# DeMux2.net
KiCad netlist of a schematic drawn in EAGLE
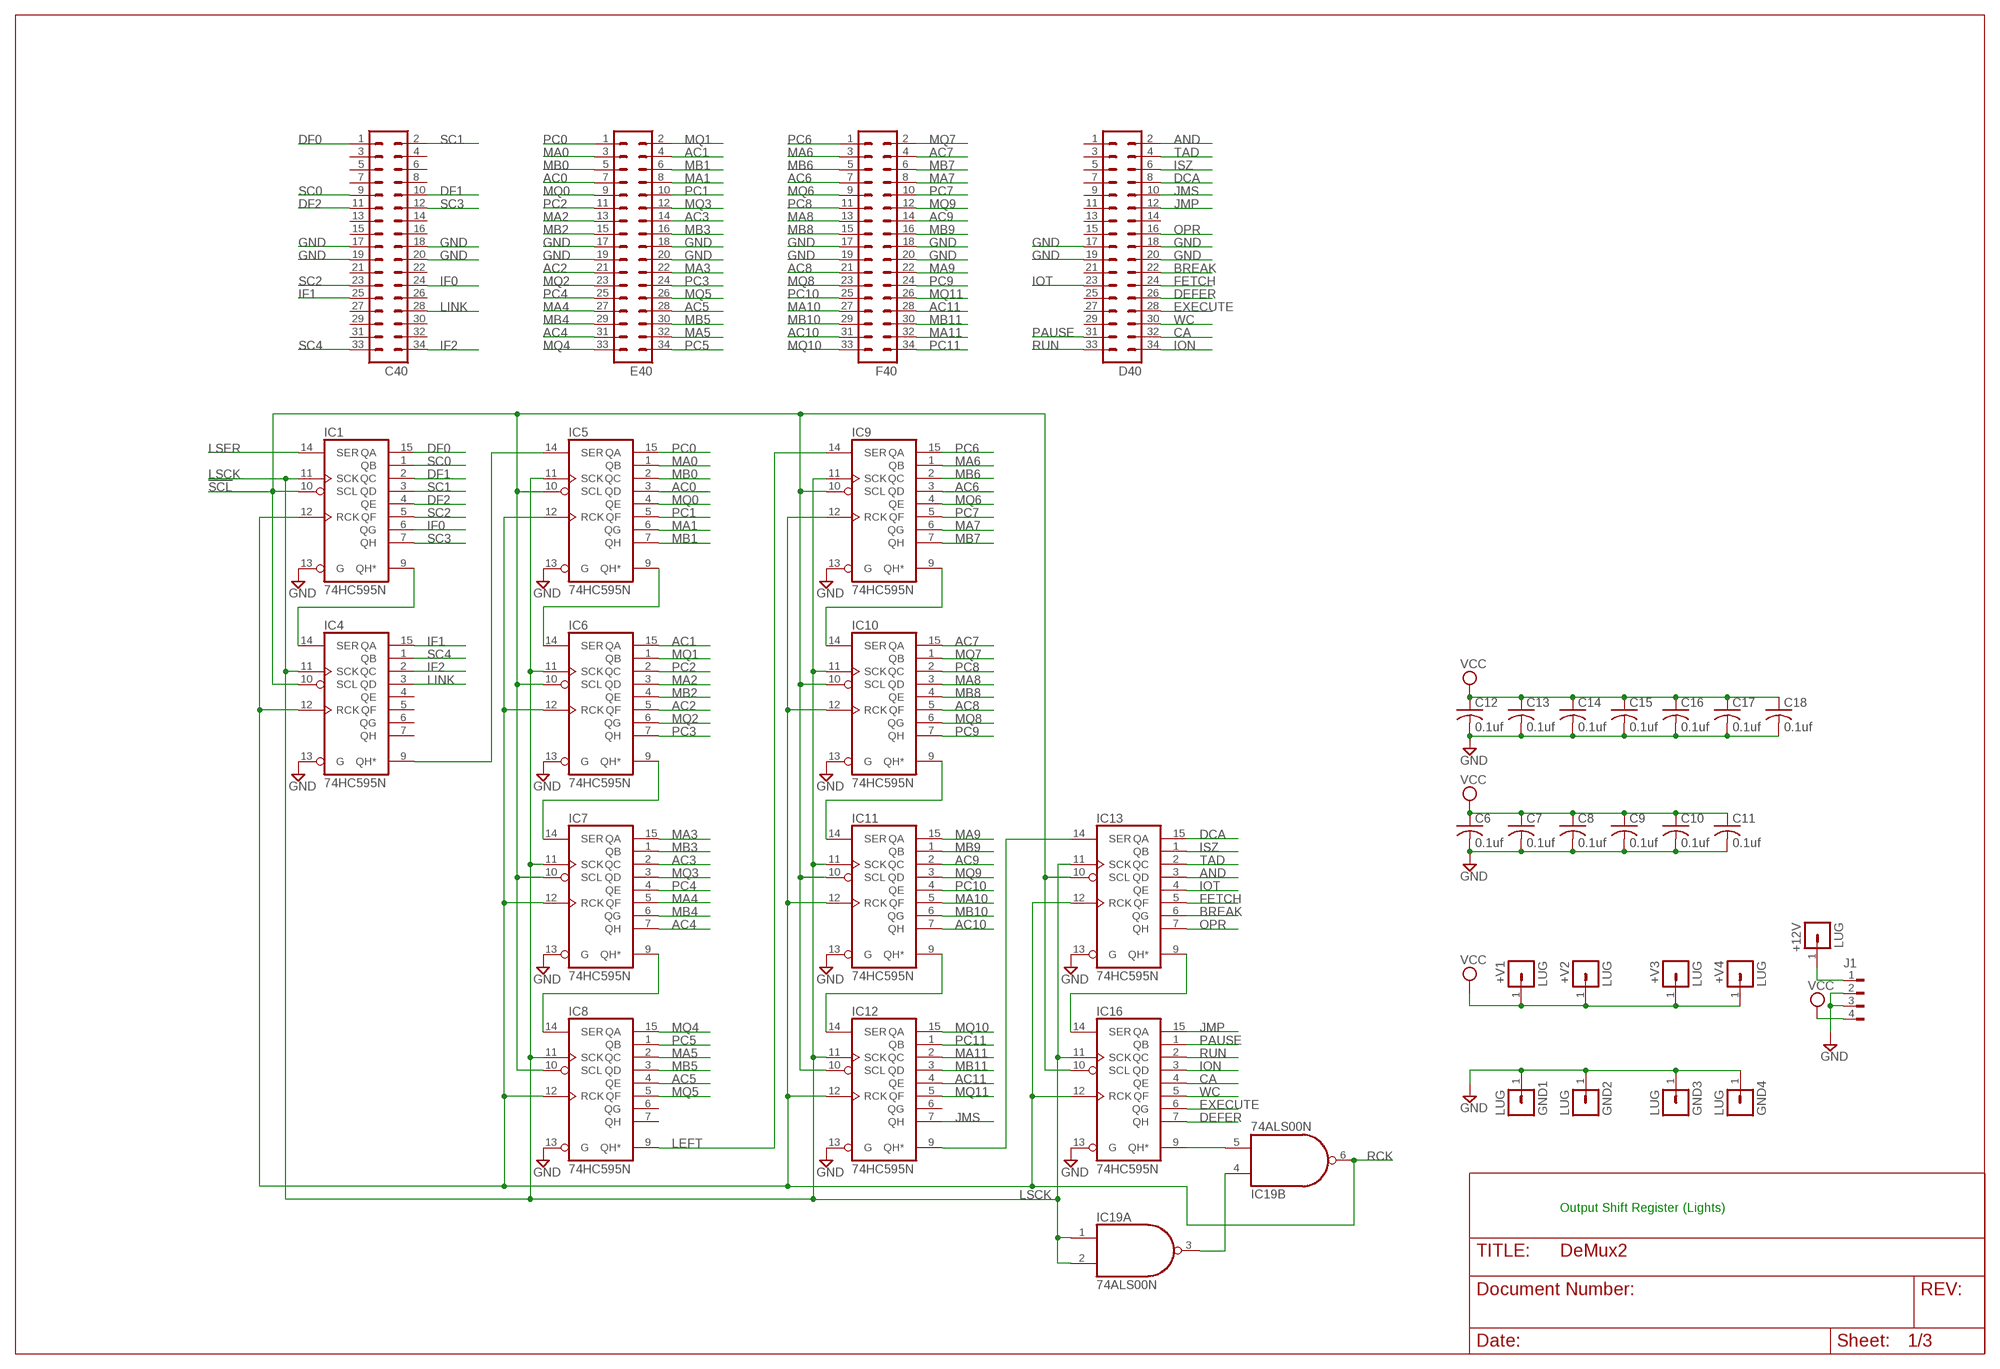
[diagram p0: schematic, sheet 1]
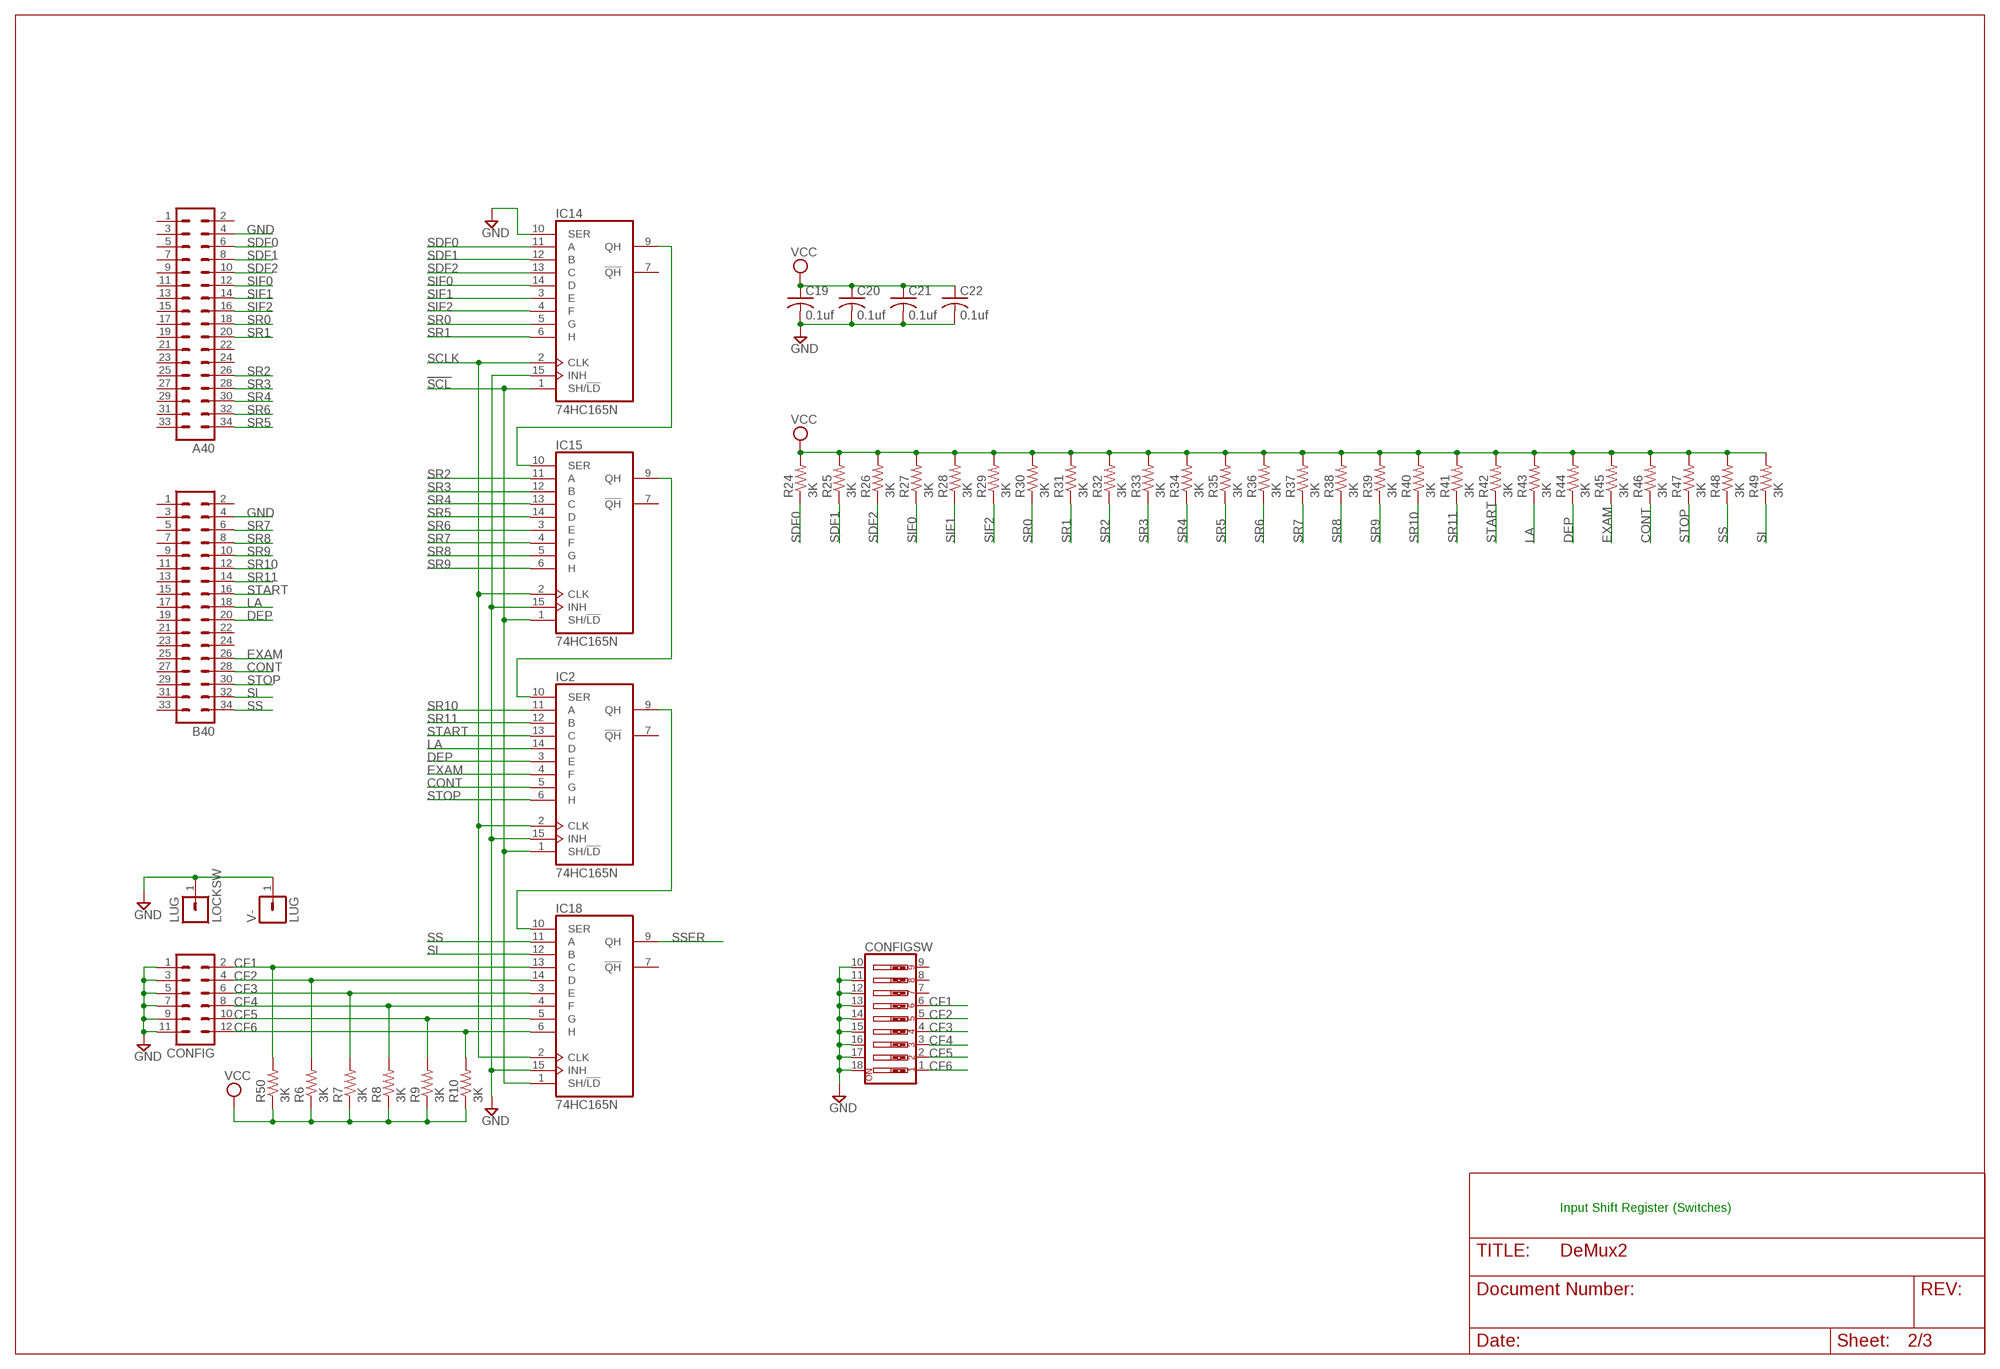
[diagram p1: schematic, sheet 2]
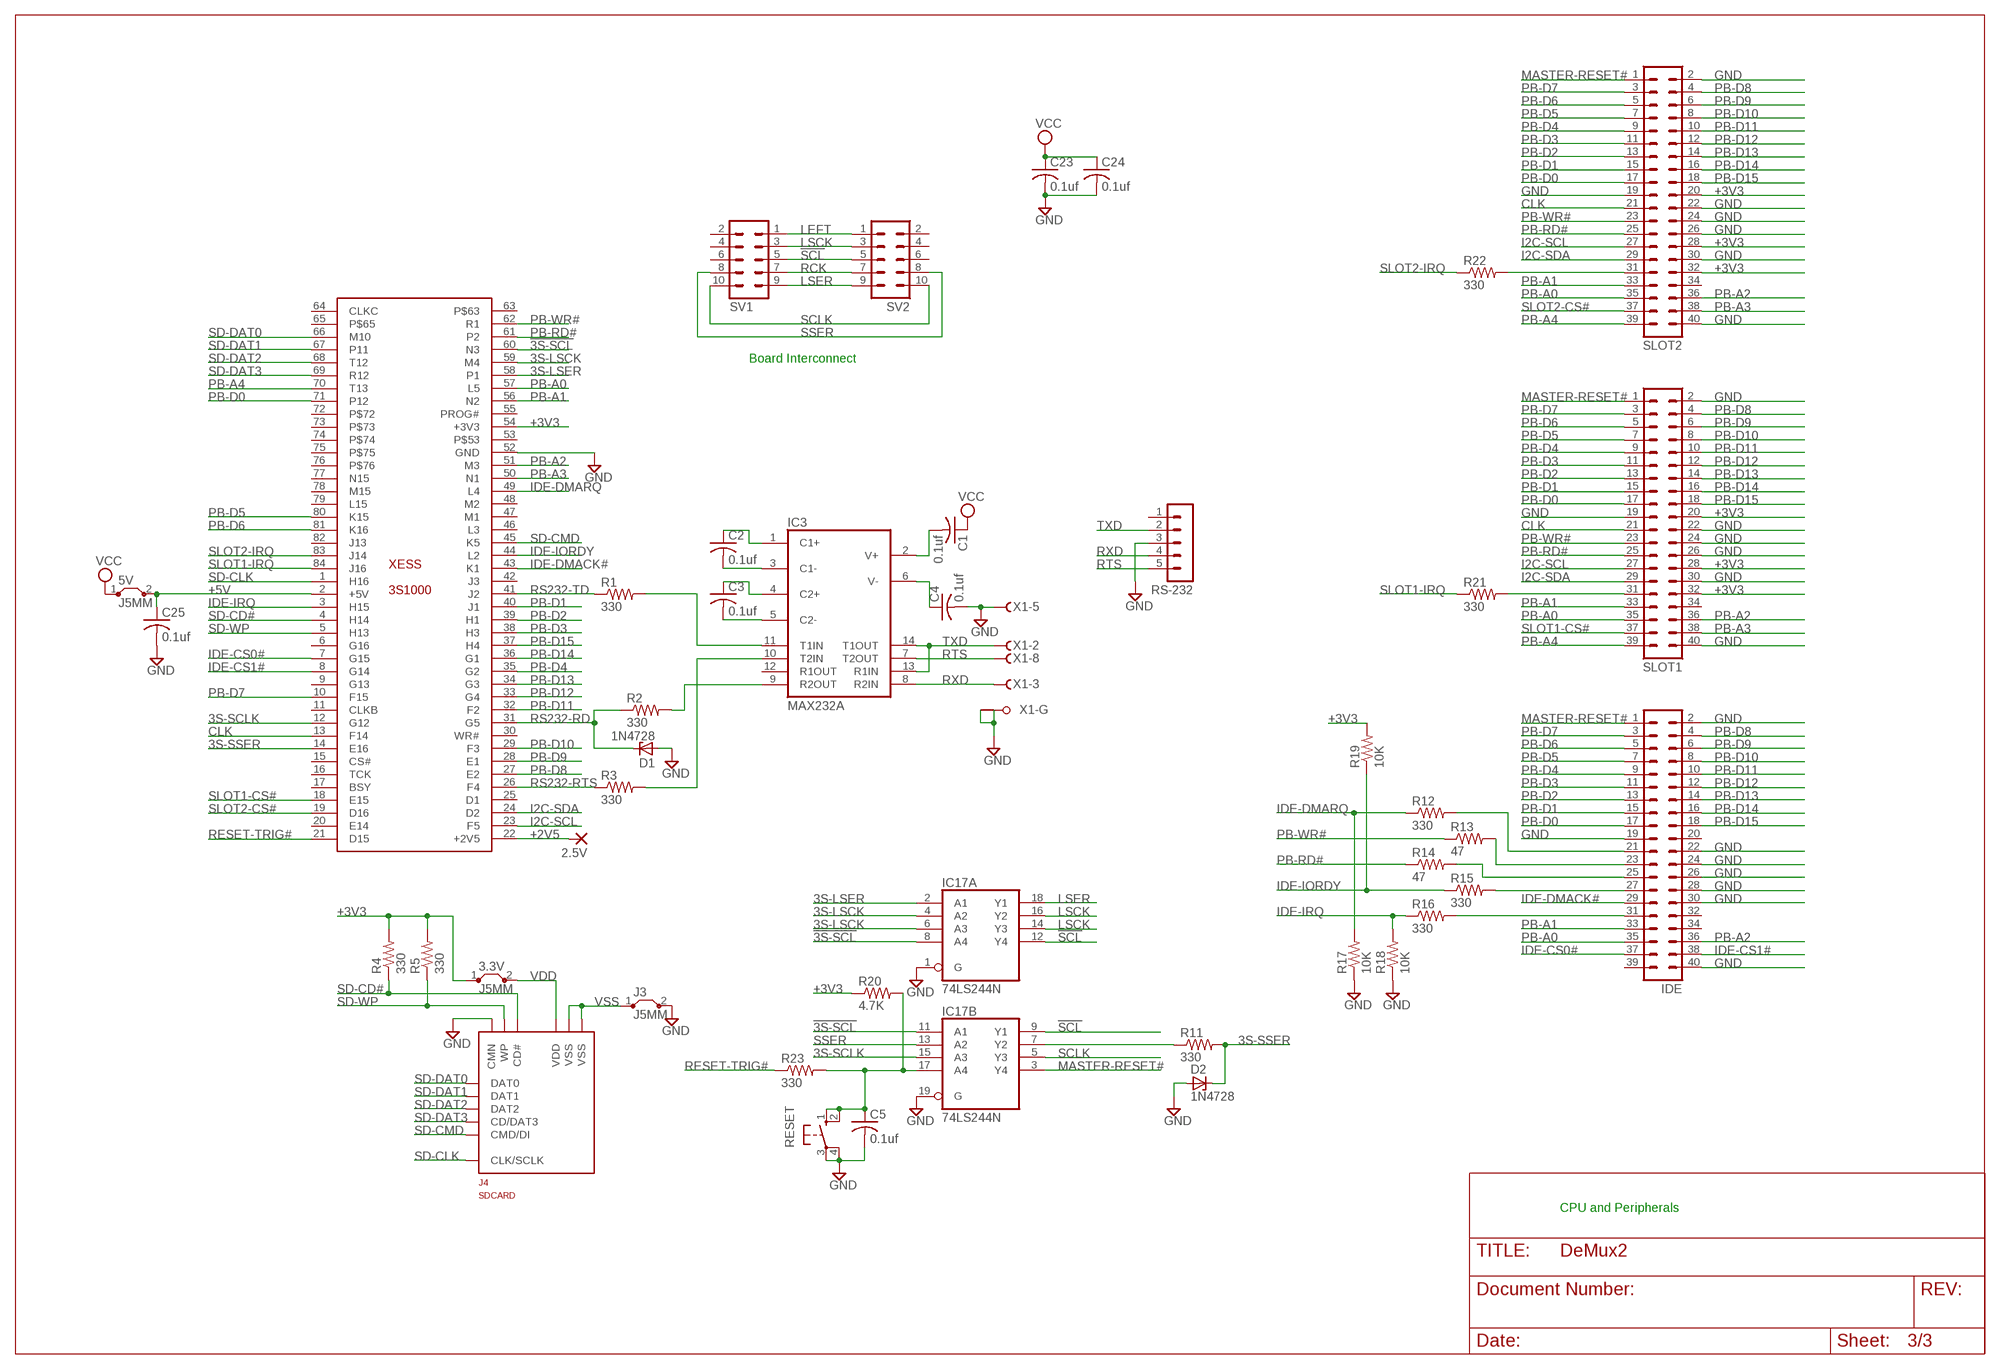
[diagram p2: schematic, sheet 3]

(export (version "E")
  (design (tool "Eeschema 10.0.6"))
  (components
    (comp (ref "2.5V")
      (value "1,6/0,8")
      (footprint "eagle-import:1,6_0,8")
      (libsource (lib "eagle-import") (part "1,6/0,8"))
    )
    (comp (ref "3.3V")
      (value "J5MM")
      (footprint "eagle-import:05")
      (libsource (lib "eagle-import") (part "J5MM"))
    )
    (comp (ref "5V")
      (value "J5MM")
      (footprint "eagle-import:05")
      (libsource (lib "eagle-import") (part "J5MM"))
    )
    (comp (ref "C1")
      (value "0.1uf")
      (footprint "eagle-import:C050-025X075")
      (libsource (lib "eagle-import") (part "C-US050-025X075"))
    )
    (comp (ref "C2")
      (value "0.1uf")
      (footprint "eagle-import:C050-025X075")
      (libsource (lib "eagle-import") (part "C-US050-025X075"))
    )
    (comp (ref "C3")
      (value "0.1uf")
      (footprint "eagle-import:C050-025X075")
      (libsource (lib "eagle-import") (part "C-US050-025X075"))
    )
    (comp (ref "C4")
      (value "0.1uf")
      (footprint "eagle-import:C050-025X075")
      (libsource (lib "eagle-import") (part "C-US050-025X075"))
    )
    (comp (ref "C5")
      (value "0.1uf")
      (footprint "eagle-import:C050-025X075")
      (libsource (lib "eagle-import") (part "C-US050-025X075"))
    )
    (comp (ref "C23")
      (value "0.1uf")
      (footprint "eagle-import:C050-025X075")
      (libsource (lib "eagle-import") (part "C-US050-025X075"))
    )
    (comp (ref "C24")
      (value "0.1uf")
      (footprint "eagle-import:C050-025X075")
      (libsource (lib "eagle-import") (part "C-US050-025X075"))
    )
    (comp (ref "C25")
      (value "0.1uf")
      (footprint "eagle-import:C050-025X075")
      (libsource (lib "eagle-import") (part "C-US050-025X075"))
    )
    (comp (ref "D1")
      (value "1N4728")
      (footprint "eagle-import:DO41Z10")
      (libsource (lib "eagle-import") (part "1N4728"))
    )
    (comp (ref "D2")
      (value "1N4728")
      (footprint "eagle-import:DO41Z10")
      (libsource (lib "eagle-import") (part "1N4728"))
    )
    (comp (ref "IC3")
      (value "MAX232A")
      (footprint "eagle-import:DIL16")
      (fields (field (name "MF") "MAXIM") (field (name "MPN") "MAX232ACPE+"))
      (libsource (lib "eagle-import") (part "MAX232"))
    )
    (comp (ref "IC17")
      (value "74LS244N")
      (footprint "eagle-import:DIL20")
      (libsource (lib "eagle-import") (part "74244NLS"))
    )
    (comp (ref "IDE")
      (value "MA20-2")
      (footprint "eagle-import:MA20-2")
      (libsource (lib "eagle-import") (part "MA20-2"))
    )
    (comp (ref "J3")
      (value "J5MM")
      (footprint "eagle-import:05")
      (libsource (lib "eagle-import") (part "J5MM"))
    )
    (comp (ref "J4")
      (value "SDCARD")
      (footprint "eagle-import:SCDA5A")
      (libsource (lib "eagle-import") (part "SDCARD"))
    )
    (comp (ref "R1")
      (value "330")
      (footprint "eagle-import:0207_10")
      (libsource (lib "eagle-import") (part "R-US_0207/10"))
    )
    (comp (ref "R2")
      (value "330")
      (footprint "eagle-import:0207_10")
      (libsource (lib "eagle-import") (part "R-US_0207/10"))
    )
    (comp (ref "R3")
      (value "330")
      (footprint "eagle-import:0207_10")
      (libsource (lib "eagle-import") (part "R-US_0207/10"))
    )
    (comp (ref "R4")
      (value "330")
      (footprint "eagle-import:0207_10")
      (libsource (lib "eagle-import") (part "R-US_0207/10"))
    )
    (comp (ref "R5")
      (value "330")
      (footprint "eagle-import:0207_10")
      (libsource (lib "eagle-import") (part "R-US_0207/10"))
    )
    (comp (ref "R11")
      (value "330")
      (footprint "eagle-import:0207_10")
      (libsource (lib "eagle-import") (part "R-US_0207/10"))
    )
    (comp (ref "R12")
      (value "330")
      (footprint "eagle-import:0207_10")
      (libsource (lib "eagle-import") (part "R-US_0207/10"))
    )
    (comp (ref "R13")
      (value "47")
      (footprint "eagle-import:0207_10")
      (libsource (lib "eagle-import") (part "R-US_0207/10"))
    )
    (comp (ref "R14")
      (value "47")
      (footprint "eagle-import:0207_10")
      (libsource (lib "eagle-import") (part "R-US_0207/10"))
    )
    (comp (ref "R15")
      (value "330")
      (footprint "eagle-import:0207_10")
      (libsource (lib "eagle-import") (part "R-US_0207/10"))
    )
    (comp (ref "R16")
      (value "330")
      (footprint "eagle-import:0207_10")
      (libsource (lib "eagle-import") (part "R-US_0207/10"))
    )
    (comp (ref "R17")
      (value "10K")
      (footprint "eagle-import:0207_10")
      (libsource (lib "eagle-import") (part "R-US_0207/10"))
    )
    (comp (ref "R18")
      (value "10K")
      (footprint "eagle-import:0207_10")
      (libsource (lib "eagle-import") (part "R-US_0207/10"))
    )
    (comp (ref "R19")
      (value "10K")
      (footprint "eagle-import:0207_10")
      (libsource (lib "eagle-import") (part "R-US_0207/10"))
    )
    (comp (ref "R20")
      (value "4.7K")
      (footprint "eagle-import:0207_10")
      (libsource (lib "eagle-import") (part "R-US_0207/10"))
    )
    (comp (ref "R21")
      (value "330")
      (footprint "eagle-import:0207_10")
      (libsource (lib "eagle-import") (part "R-US_0207/10"))
    )
    (comp (ref "R22")
      (value "330")
      (footprint "eagle-import:0207_10")
      (libsource (lib "eagle-import") (part "R-US_0207/10"))
    )
    (comp (ref "R23")
      (value "330")
      (footprint "eagle-import:0207_10")
      (libsource (lib "eagle-import") (part "R-US_0207/10"))
    )
    (comp (ref "RESET")
      (value "40-XX")
      (footprint "eagle-import:B3F-40XX")
      (fields (field (name "MF") "OMRON COMPONENTS USA") (field (name "MPN") "B3F-4000"))
      (libsource (lib "eagle-import") (part "40-XX"))
    )
    (comp (ref "RS-232")
      (value "MA05-1")
      (footprint "eagle-import:MA05-1")
      (libsource (lib "eagle-import") (part "MA05-1"))
    )
    (comp (ref "SLOT1")
      (value "MA20-2")
      (footprint "eagle-import:MA20-2")
      (libsource (lib "eagle-import") (part "MA20-2"))
    )
    (comp (ref "SLOT2")
      (value "MA20-2")
      (footprint "eagle-import:MA20-2")
      (libsource (lib "eagle-import") (part "MA20-2"))
    )
    (comp (ref "SV1")
      (value "MA05-2")
      (footprint "eagle-import:MA05-2")
      (libsource (lib "eagle-import") (part "MA05-2"))
    )
    (comp (ref "SV2")
      (value "MA05-2")
      (footprint "eagle-import:MA05-2")
      (libsource (lib "eagle-import") (part "MA05-2"))
    )
    (comp (ref "X1")
      (value "F09HPS")
      (footprint "eagle-import:F09HP")
      (libsource (lib "eagle-import") (part "F09HPS"))
    )
    (comp (ref "XESS")
      (value "3S1000")
      (footprint "eagle-import:3S1000")
      (libsource (lib "eagle-import") (part "3S1000"))
    )
    (comp (ref "+12V")
      (value "LUG")
      (footprint "eagle-import:SPADELUG")
      (libsource (lib "eagle-import") (part "LUG"))
    )
    (comp (ref "+V1")
      (value "LUG")
      (footprint "eagle-import:SPADELUG")
      (libsource (lib "eagle-import") (part "LUG"))
    )
    (comp (ref "+V2")
      (value "LUG")
      (footprint "eagle-import:SPADELUG")
      (libsource (lib "eagle-import") (part "LUG"))
    )
    (comp (ref "+V3")
      (value "LUG")
      (footprint "eagle-import:SPADELUG")
      (libsource (lib "eagle-import") (part "LUG"))
    )
    (comp (ref "+V4")
      (value "LUG")
      (footprint "eagle-import:SPADELUG")
      (libsource (lib "eagle-import") (part "LUG"))
    )
    (comp (ref "C6")
      (value "0.1uf")
      (footprint "eagle-import:C050-025X075")
      (libsource (lib "eagle-import") (part "C-US050-025X075"))
    )
    (comp (ref "C7")
      (value "0.1uf")
      (footprint "eagle-import:C050-025X075")
      (libsource (lib "eagle-import") (part "C-US050-025X075"))
    )
    (comp (ref "C8")
      (value "0.1uf")
      (footprint "eagle-import:C050-025X075")
      (libsource (lib "eagle-import") (part "C-US050-025X075"))
    )
    (comp (ref "C9")
      (value "0.1uf")
      (footprint "eagle-import:C050-025X075")
      (libsource (lib "eagle-import") (part "C-US050-025X075"))
    )
    (comp (ref "C10")
      (value "0.1uf")
      (footprint "eagle-import:C050-025X075")
      (libsource (lib "eagle-import") (part "C-US050-025X075"))
    )
    (comp (ref "C11")
      (value "0.1uf")
      (footprint "eagle-import:C050-025X075")
      (libsource (lib "eagle-import") (part "C-US050-025X075"))
    )
    (comp (ref "C12")
      (value "0.1uf")
      (footprint "eagle-import:C050-025X075")
      (libsource (lib "eagle-import") (part "C-US050-025X075"))
    )
    (comp (ref "C13")
      (value "0.1uf")
      (footprint "eagle-import:C050-025X075")
      (libsource (lib "eagle-import") (part "C-US050-025X075"))
    )
    (comp (ref "C14")
      (value "0.1uf")
      (footprint "eagle-import:C050-025X075")
      (libsource (lib "eagle-import") (part "C-US050-025X075"))
    )
    (comp (ref "C15")
      (value "0.1uf")
      (footprint "eagle-import:C050-025X075")
      (libsource (lib "eagle-import") (part "C-US050-025X075"))
    )
    (comp (ref "C16")
      (value "0.1uf")
      (footprint "eagle-import:C050-025X075")
      (libsource (lib "eagle-import") (part "C-US050-025X075"))
    )
    (comp (ref "C17")
      (value "0.1uf")
      (footprint "eagle-import:C050-025X075")
      (libsource (lib "eagle-import") (part "C-US050-025X075"))
    )
    (comp (ref "C18")
      (value "0.1uf")
      (footprint "eagle-import:C050-025X075")
      (libsource (lib "eagle-import") (part "C-US050-025X075"))
    )
    (comp (ref "C40")
      (value "MA17-2")
      (footprint "eagle-import:MA17-2")
      (libsource (lib "eagle-import") (part "MA17-2"))
    )
    (comp (ref "D40")
      (value "MA17-2")
      (footprint "eagle-import:MA17-2")
      (libsource (lib "eagle-import") (part "MA17-2"))
    )
    (comp (ref "E40")
      (value "MA17-2")
      (footprint "eagle-import:MA17-2")
      (libsource (lib "eagle-import") (part "MA17-2"))
    )
    (comp (ref "F40")
      (value "MA17-2")
      (footprint "eagle-import:MA17-2")
      (libsource (lib "eagle-import") (part "MA17-2"))
    )
    (comp (ref "GND1")
      (value "LUG")
      (footprint "eagle-import:SPADELUG")
      (libsource (lib "eagle-import") (part "LUG"))
    )
    (comp (ref "GND2")
      (value "LUG")
      (footprint "eagle-import:SPADELUG")
      (libsource (lib "eagle-import") (part "LUG"))
    )
    (comp (ref "GND3")
      (value "LUG")
      (footprint "eagle-import:SPADELUG")
      (libsource (lib "eagle-import") (part "LUG"))
    )
    (comp (ref "GND4")
      (value "LUG")
      (footprint "eagle-import:SPADELUG")
      (libsource (lib "eagle-import") (part "LUG"))
    )
    (comp (ref "IC1")
      (value "74HC595N")
      (footprint "eagle-import:DIL16")
      (libsource (lib "eagle-import") (part "74595NLS"))
    )
    (comp (ref "IC4")
      (value "74HC595N")
      (footprint "eagle-import:DIL16")
      (libsource (lib "eagle-import") (part "74595NLS"))
    )
    (comp (ref "IC5")
      (value "74HC595N")
      (footprint "eagle-import:DIL16")
      (libsource (lib "eagle-import") (part "74595NLS"))
    )
    (comp (ref "IC6")
      (value "74HC595N")
      (footprint "eagle-import:DIL16")
      (libsource (lib "eagle-import") (part "74595NLS"))
    )
    (comp (ref "IC7")
      (value "74HC595N")
      (footprint "eagle-import:DIL16")
      (libsource (lib "eagle-import") (part "74595NLS"))
    )
    (comp (ref "IC8")
      (value "74HC595N")
      (footprint "eagle-import:DIL16")
      (libsource (lib "eagle-import") (part "74595NLS"))
    )
    (comp (ref "IC9")
      (value "74HC595N")
      (footprint "eagle-import:DIL16")
      (libsource (lib "eagle-import") (part "74595NLS"))
    )
    (comp (ref "IC10")
      (value "74HC595N")
      (footprint "eagle-import:DIL16")
      (libsource (lib "eagle-import") (part "74595NLS"))
    )
    (comp (ref "IC11")
      (value "74HC595N")
      (footprint "eagle-import:DIL16")
      (libsource (lib "eagle-import") (part "74595NLS"))
    )
    (comp (ref "IC12")
      (value "74HC595N")
      (footprint "eagle-import:DIL16")
      (libsource (lib "eagle-import") (part "74595NLS"))
    )
    (comp (ref "IC13")
      (value "74HC595N")
      (footprint "eagle-import:DIL16")
      (libsource (lib "eagle-import") (part "74595NLS"))
    )
    (comp (ref "IC16")
      (value "74HC595N")
      (footprint "eagle-import:DIL16")
      (libsource (lib "eagle-import") (part "74595NLS"))
    )
    (comp (ref "IC19")
      (value "74ALS00N")
      (footprint "eagle-import:DIL14")
      (libsource (lib "eagle-import") (part "7400NALS"))
    )
    (comp (ref "J1")
      (value "FLOPPY-4")
      (footprint "eagle-import:FLOPPY-4")
      (libsource (lib "eagle-import") (part "FLOPPY-4"))
    )
    (comp (ref "A40")
      (value "MA17-2")
      (footprint "eagle-import:MA17-2")
      (libsource (lib "eagle-import") (part "MA17-2"))
    )
    (comp (ref "B40")
      (value "MA17-2")
      (footprint "eagle-import:MA17-2")
      (libsource (lib "eagle-import") (part "MA17-2"))
    )
    (comp (ref "C19")
      (value "0.1uf")
      (footprint "eagle-import:C050-025X075")
      (libsource (lib "eagle-import") (part "C-US050-025X075"))
    )
    (comp (ref "C20")
      (value "0.1uf")
      (footprint "eagle-import:C050-025X075")
      (libsource (lib "eagle-import") (part "C-US050-025X075"))
    )
    (comp (ref "C21")
      (value "0.1uf")
      (footprint "eagle-import:C050-025X075")
      (libsource (lib "eagle-import") (part "C-US050-025X075"))
    )
    (comp (ref "C22")
      (value "0.1uf")
      (footprint "eagle-import:C050-025X075")
      (libsource (lib "eagle-import") (part "C-US050-025X075"))
    )
    (comp (ref "CONFIG")
      (value "MA06-2")
      (footprint "eagle-import:MA06-2")
      (libsource (lib "eagle-import") (part "MA06-2"))
    )
    (comp (ref "CONFIGSW")
      (value "SW_DIP-9")
      (footprint "eagle-import:EDG-09")
      (libsource (lib "eagle-import") (part "SW_DIP-9"))
    )
    (comp (ref "IC2")
      (value "74HC165N")
      (footprint "eagle-import:DIL16")
      (libsource (lib "eagle-import") (part "74165NLS"))
    )
    (comp (ref "IC14")
      (value "74HC165N")
      (footprint "eagle-import:DIL16")
      (libsource (lib "eagle-import") (part "74165NLS"))
    )
    (comp (ref "IC15")
      (value "74HC165N")
      (footprint "eagle-import:DIL16")
      (libsource (lib "eagle-import") (part "74165NLS"))
    )
    (comp (ref "IC18")
      (value "74HC165N")
      (footprint "eagle-import:DIL16")
      (libsource (lib "eagle-import") (part "74165NLS"))
    )
    (comp (ref "LOCKSW")
      (value "LUG")
      (footprint "eagle-import:SPADELUG")
      (libsource (lib "eagle-import") (part "LUG"))
    )
    (comp (ref "R6")
      (value "3K")
      (footprint "eagle-import:0207_10")
      (libsource (lib "eagle-import") (part "R-US_0207/10"))
    )
    (comp (ref "R7")
      (value "3K")
      (footprint "eagle-import:0207_10")
      (libsource (lib "eagle-import") (part "R-US_0207/10"))
    )
    (comp (ref "R8")
      (value "3K")
      (footprint "eagle-import:0207_10")
      (libsource (lib "eagle-import") (part "R-US_0207/10"))
    )
    (comp (ref "R9")
      (value "3K")
      (footprint "eagle-import:0207_10")
      (libsource (lib "eagle-import") (part "R-US_0207/10"))
    )
    (comp (ref "R10")
      (value "3K")
      (footprint "eagle-import:0207_10")
      (libsource (lib "eagle-import") (part "R-US_0207/10"))
    )
    (comp (ref "R24")
      (value "3K")
      (footprint "eagle-import:0207_10")
      (libsource (lib "eagle-import") (part "R-US_0207/10"))
    )
    (comp (ref "R25")
      (value "3K")
      (footprint "eagle-import:0207_10")
      (libsource (lib "eagle-import") (part "R-US_0207/10"))
    )
    (comp (ref "R26")
      (value "3K")
      (footprint "eagle-import:0207_10")
      (libsource (lib "eagle-import") (part "R-US_0207/10"))
    )
    (comp (ref "R27")
      (value "3K")
      (footprint "eagle-import:0207_10")
      (libsource (lib "eagle-import") (part "R-US_0207/10"))
    )
    (comp (ref "R28")
      (value "3K")
      (footprint "eagle-import:0207_10")
      (libsource (lib "eagle-import") (part "R-US_0207/10"))
    )
    (comp (ref "R29")
      (value "3K")
      (footprint "eagle-import:0207_10")
      (libsource (lib "eagle-import") (part "R-US_0207/10"))
    )
    (comp (ref "R30")
      (value "3K")
      (footprint "eagle-import:0207_10")
      (libsource (lib "eagle-import") (part "R-US_0207/10"))
    )
    (comp (ref "R31")
      (value "3K")
      (footprint "eagle-import:0207_10")
      (libsource (lib "eagle-import") (part "R-US_0207/10"))
    )
    (comp (ref "R32")
      (value "3K")
      (footprint "eagle-import:0207_10")
      (libsource (lib "eagle-import") (part "R-US_0207/10"))
    )
    (comp (ref "R33")
      (value "3K")
      (footprint "eagle-import:0207_10")
      (libsource (lib "eagle-import") (part "R-US_0207/10"))
    )
    (comp (ref "R34")
      (value "3K")
      (footprint "eagle-import:0207_10")
      (libsource (lib "eagle-import") (part "R-US_0207/10"))
    )
    (comp (ref "R35")
      (value "3K")
      (footprint "eagle-import:0207_10")
      (libsource (lib "eagle-import") (part "R-US_0207/10"))
    )
    (comp (ref "R36")
      (value "3K")
      (footprint "eagle-import:0207_10")
      (libsource (lib "eagle-import") (part "R-US_0207/10"))
    )
    (comp (ref "R37")
      (value "3K")
      (footprint "eagle-import:0207_10")
      (libsource (lib "eagle-import") (part "R-US_0207/10"))
    )
    (comp (ref "R38")
      (value "3K")
      (footprint "eagle-import:0207_10")
      (libsource (lib "eagle-import") (part "R-US_0207/10"))
    )
    (comp (ref "R39")
      (value "3K")
      (footprint "eagle-import:0207_10")
      (libsource (lib "eagle-import") (part "R-US_0207/10"))
    )
    (comp (ref "R40")
      (value "3K")
      (footprint "eagle-import:0207_10")
      (libsource (lib "eagle-import") (part "R-US_0207/10"))
    )
    (comp (ref "R41")
      (value "3K")
      (footprint "eagle-import:0207_10")
      (libsource (lib "eagle-import") (part "R-US_0207/10"))
    )
    (comp (ref "R42")
      (value "3K")
      (footprint "eagle-import:0207_10")
      (libsource (lib "eagle-import") (part "R-US_0207/10"))
    )
    (comp (ref "R43")
      (value "3K")
      (footprint "eagle-import:0207_10")
      (libsource (lib "eagle-import") (part "R-US_0207/10"))
    )
    (comp (ref "R44")
      (value "3K")
      (footprint "eagle-import:0207_10")
      (libsource (lib "eagle-import") (part "R-US_0207/10"))
    )
    (comp (ref "R45")
      (value "3K")
      (footprint "eagle-import:0207_10")
      (libsource (lib "eagle-import") (part "R-US_0207/10"))
    )
    (comp (ref "R46")
      (value "3K")
      (footprint "eagle-import:0207_10")
      (libsource (lib "eagle-import") (part "R-US_0207/10"))
    )
    (comp (ref "R47")
      (value "3K")
      (footprint "eagle-import:0207_10")
      (libsource (lib "eagle-import") (part "R-US_0207/10"))
    )
    (comp (ref "R48")
      (value "3K")
      (footprint "eagle-import:0207_10")
      (libsource (lib "eagle-import") (part "R-US_0207/10"))
    )
    (comp (ref "R49")
      (value "3K")
      (footprint "eagle-import:0207_10")
      (libsource (lib "eagle-import") (part "R-US_0207/10"))
    )
    (comp (ref "R50")
      (value "3K")
      (footprint "eagle-import:0207_10")
      (libsource (lib "eagle-import") (part "R-US_0207/10"))
    )
    (comp (ref "V-")
      (value "LUG")
      (footprint "eagle-import:SPADELUG")
      (libsource (lib "eagle-import") (part "LUG"))
    )
  )
  (nets
    (net (code "1") (name "+2V5") (class "Default")
      (node (ref "2.5V") (pin "1") (pinfunction "P_1") (pintype "passive"))
      (node (ref "XESS") (pin "22") (pinfunction "+2V5_22") (pintype "power_in"))
    )
    (net (code "2") (name "+3V3") (class "Default")
      (node (ref "3.3V") (pin "1") (pinfunction "1_1") (pintype "passive"))
      (node (ref "R19") (pin "2") (pinfunction "2_2") (pintype "passive"))
      (node (ref "R20") (pin "1") (pinfunction "1_1") (pintype "passive"))
      (node (ref "R4") (pin "2") (pinfunction "2_2") (pintype "passive"))
      (node (ref "R5") (pin "2") (pinfunction "2_2") (pintype "passive"))
      (node (ref "SLOT1") (pin "20") (pinfunction "20_20") (pintype "passive"))
      (node (ref "SLOT1") (pin "28") (pinfunction "28_28") (pintype "passive"))
      (node (ref "SLOT1") (pin "32") (pinfunction "32_32") (pintype "passive"))
      (node (ref "SLOT2") (pin "20") (pinfunction "20_20") (pintype "passive"))
      (node (ref "SLOT2") (pin "28") (pinfunction "28_28") (pintype "passive"))
      (node (ref "SLOT2") (pin "32") (pinfunction "32_32") (pintype "passive"))
      (node (ref "XESS") (pin "54") (pinfunction "+3V3_54") (pintype "power_in"))
    )
    (net (code "3") (name "+5V") (class "Default")
      (node (ref "5V") (pin "2") (pinfunction "2_2") (pintype "passive"))
      (node (ref "C25") (pin "1") (pinfunction "1_1") (pintype "passive"))
      (node (ref "XESS") (pin "2") (pinfunction "+5V_2") (pintype "power_in"))
    )
    (net (code "4") (name "3S-LSCK") (class "Default")
      (node (ref "IC17") (pin "4") (pinfunction "A2_4") (pintype "input"))
      (node (ref "IC17") (pin "6") (pinfunction "A3_6") (pintype "input"))
      (node (ref "XESS") (pin "59") (pinfunction "M4_59") (pintype "bidirectional"))
    )
    (net (code "5") (name "3S-LSER") (class "Default")
      (node (ref "IC17") (pin "2") (pinfunction "A1_2") (pintype "input"))
      (node (ref "XESS") (pin "58") (pinfunction "P1_58") (pintype "bidirectional"))
    )
    (net (code "6") (name "3S-SCLK") (class "Default")
      (node (ref "IC17") (pin "15") (pinfunction "A3_15") (pintype "input"))
      (node (ref "XESS") (pin "12") (pinfunction "G12_12") (pintype "bidirectional"))
    )
    (net (code "7") (name "3S-SSER") (class "Default")
      (node (ref "D2") (pin "C") (pinfunction "C_C") (pintype "passive"))
      (node (ref "R11") (pin "2") (pinfunction "2_2") (pintype "passive"))
      (node (ref "XESS") (pin "14") (pinfunction "E16_14") (pintype "bidirectional"))
    )
    (net (code "8") (name "AC0") (class "Default")
      (node (ref "E40") (pin "7") (pinfunction "7_7") (pintype "passive"))
      (node (ref "IC5") (pin "3") (pinfunction "QD_3") (pintype "tri_state"))
    )
    (net (code "9") (name "AC1") (class "Default")
      (node (ref "E40") (pin "4") (pinfunction "4_4") (pintype "passive"))
      (node (ref "IC6") (pin "15") (pinfunction "QA_15") (pintype "tri_state"))
    )
    (net (code "10") (name "AC2") (class "Default")
      (node (ref "E40") (pin "21") (pinfunction "21_21") (pintype "passive"))
      (node (ref "IC6") (pin "5") (pinfunction "QF_5") (pintype "tri_state"))
    )
    (net (code "11") (name "AC3") (class "Default")
      (node (ref "E40") (pin "14") (pinfunction "14_14") (pintype "passive"))
      (node (ref "IC7") (pin "2") (pinfunction "QC_2") (pintype "tri_state"))
    )
    (net (code "12") (name "AC4") (class "Default")
      (node (ref "E40") (pin "31") (pinfunction "31_31") (pintype "passive"))
      (node (ref "IC7") (pin "7") (pinfunction "QH_7") (pintype "tri_state"))
    )
    (net (code "13") (name "AC5") (class "Default")
      (node (ref "E40") (pin "28") (pinfunction "28_28") (pintype "passive"))
      (node (ref "IC8") (pin "4") (pinfunction "QE_4") (pintype "tri_state"))
    )
    (net (code "14") (name "AC6") (class "Default")
      (node (ref "F40") (pin "7") (pinfunction "7_7") (pintype "passive"))
      (node (ref "IC9") (pin "3") (pinfunction "QD_3") (pintype "tri_state"))
    )
    (net (code "15") (name "AC7") (class "Default")
      (node (ref "F40") (pin "4") (pinfunction "4_4") (pintype "passive"))
      (node (ref "IC10") (pin "15") (pinfunction "QA_15") (pintype "tri_state"))
    )
    (net (code "16") (name "AC8") (class "Default")
      (node (ref "F40") (pin "21") (pinfunction "21_21") (pintype "passive"))
      (node (ref "IC10") (pin "5") (pinfunction "QF_5") (pintype "tri_state"))
    )
    (net (code "17") (name "AC9") (class "Default")
      (node (ref "F40") (pin "14") (pinfunction "14_14") (pintype "passive"))
      (node (ref "IC11") (pin "2") (pinfunction "QC_2") (pintype "tri_state"))
    )
    (net (code "18") (name "AC10") (class "Default")
      (node (ref "F40") (pin "31") (pinfunction "31_31") (pintype "passive"))
      (node (ref "IC11") (pin "7") (pinfunction "QH_7") (pintype "tri_state"))
    )
    (net (code "19") (name "AC11") (class "Default")
      (node (ref "F40") (pin "28") (pinfunction "28_28") (pintype "passive"))
      (node (ref "IC12") (pin "4") (pinfunction "QE_4") (pintype "tri_state"))
    )
    (net (code "20") (name "AND") (class "Default")
      (node (ref "D40") (pin "2") (pinfunction "2_2") (pintype "passive"))
      (node (ref "IC13") (pin "3") (pinfunction "QD_3") (pintype "tri_state"))
    )
    (net (code "21") (name "BREAK") (class "Default")
      (node (ref "D40") (pin "22") (pinfunction "22_22") (pintype "passive"))
      (node (ref "IC13") (pin "6") (pinfunction "QG_6") (pintype "tri_state"))
    )
    (net (code "22") (name "CA") (class "Default")
      (node (ref "D40") (pin "32") (pinfunction "32_32") (pintype "passive"))
      (node (ref "IC16") (pin "4") (pinfunction "QE_4") (pintype "tri_state"))
    )
    (net (code "23") (name "CF1") (class "Default")
      (node (ref "CONFIG") (pin "2") (pinfunction "2_2") (pintype "passive"))
      (node (ref "CONFIGSW") (pin "6") (pinfunction "6_6") (pintype "passive"))
      (node (ref "IC18") (pin "13") (pinfunction "C_13") (pintype "input"))
      (node (ref "R50") (pin "2") (pinfunction "2_2") (pintype "passive"))
    )
    (net (code "24") (name "CF2") (class "Default")
      (node (ref "CONFIG") (pin "4") (pinfunction "4_4") (pintype "passive"))
      (node (ref "CONFIGSW") (pin "5") (pinfunction "5_5") (pintype "passive"))
      (node (ref "IC18") (pin "14") (pinfunction "D_14") (pintype "input"))
      (node (ref "R6") (pin "2") (pinfunction "2_2") (pintype "passive"))
    )
    (net (code "25") (name "CF3") (class "Default")
      (node (ref "CONFIG") (pin "6") (pinfunction "6_6") (pintype "passive"))
      (node (ref "CONFIGSW") (pin "4") (pinfunction "4_4") (pintype "passive"))
      (node (ref "IC18") (pin "3") (pinfunction "E_3") (pintype "input"))
      (node (ref "R7") (pin "2") (pinfunction "2_2") (pintype "passive"))
    )
    (net (code "26") (name "CF4") (class "Default")
      (node (ref "CONFIG") (pin "8") (pinfunction "8_8") (pintype "passive"))
      (node (ref "CONFIGSW") (pin "3") (pinfunction "3_3") (pintype "passive"))
      (node (ref "IC18") (pin "4") (pinfunction "F_4") (pintype "input"))
      (node (ref "R8") (pin "2") (pinfunction "2_2") (pintype "passive"))
    )
    (net (code "27") (name "CF5") (class "Default")
      (node (ref "CONFIG") (pin "10") (pinfunction "10_10") (pintype "passive"))
      (node (ref "CONFIGSW") (pin "2") (pinfunction "2_2") (pintype "passive"))
      (node (ref "IC18") (pin "5") (pinfunction "G_5") (pintype "input"))
      (node (ref "R9") (pin "2") (pinfunction "2_2") (pintype "passive"))
    )
    (net (code "28") (name "CF6") (class "Default")
      (node (ref "CONFIG") (pin "12") (pinfunction "12_12") (pintype "passive"))
      (node (ref "CONFIGSW") (pin "1") (pinfunction "1_1") (pintype "passive"))
      (node (ref "IC18") (pin "6") (pinfunction "H_6") (pintype "input"))
      (node (ref "R10") (pin "2") (pinfunction "2_2") (pintype "passive"))
    )
    (net (code "29") (name "CLK") (class "Default")
      (node (ref "SLOT1") (pin "21") (pinfunction "21_21") (pintype "passive"))
      (node (ref "SLOT2") (pin "21") (pinfunction "21_21") (pintype "passive"))
      (node (ref "XESS") (pin "13") (pinfunction "F14_13") (pintype "bidirectional"))
    )
    (net (code "30") (name "CONT") (class "Default")
      (node (ref "B40") (pin "28") (pinfunction "28_28") (pintype "passive"))
      (node (ref "IC2") (pin "5") (pinfunction "G_5") (pintype "input"))
      (node (ref "R46") (pin "1") (pinfunction "1_1") (pintype "passive"))
    )
    (net (code "31") (name "DCA") (class "Default")
      (node (ref "D40") (pin "8") (pinfunction "8_8") (pintype "passive"))
      (node (ref "IC13") (pin "15") (pinfunction "QA_15") (pintype "tri_state"))
    )
    (net (code "32") (name "DEFER") (class "Default")
      (node (ref "D40") (pin "26") (pinfunction "26_26") (pintype "passive"))
      (node (ref "IC16") (pin "7") (pinfunction "QH_7") (pintype "tri_state"))
    )
    (net (code "33") (name "DEP") (class "Default")
      (node (ref "B40") (pin "20") (pinfunction "20_20") (pintype "passive"))
      (node (ref "IC2") (pin "3") (pinfunction "E_3") (pintype "input"))
      (node (ref "R44") (pin "1") (pinfunction "1_1") (pintype "passive"))
    )
    (net (code "34") (name "DF0") (class "Default")
      (node (ref "C40") (pin "1") (pinfunction "1_1") (pintype "passive"))
      (node (ref "IC1") (pin "15") (pinfunction "QA_15") (pintype "tri_state"))
    )
    (net (code "35") (name "DF1") (class "Default")
      (node (ref "C40") (pin "10") (pinfunction "10_10") (pintype "passive"))
      (node (ref "IC1") (pin "2") (pinfunction "QC_2") (pintype "tri_state"))
    )
    (net (code "36") (name "DF2") (class "Default")
      (node (ref "C40") (pin "11") (pinfunction "11_11") (pintype "passive"))
      (node (ref "IC1") (pin "4") (pinfunction "QE_4") (pintype "tri_state"))
    )
    (net (code "37") (name "EXAM") (class "Default")
      (node (ref "B40") (pin "26") (pinfunction "26_26") (pintype "passive"))
      (node (ref "IC2") (pin "4") (pinfunction "F_4") (pintype "input"))
      (node (ref "R45") (pin "1") (pinfunction "1_1") (pintype "passive"))
    )
    (net (code "38") (name "EXECUTE") (class "Default")
      (node (ref "D40") (pin "28") (pinfunction "28_28") (pintype "passive"))
      (node (ref "IC16") (pin "6") (pinfunction "QG_6") (pintype "tri_state"))
    )
    (net (code "39") (name "FETCH") (class "Default")
      (node (ref "D40") (pin "24") (pinfunction "24_24") (pintype "passive"))
      (node (ref "IC13") (pin "5") (pinfunction "QF_5") (pintype "tri_state"))
    )
    (net (code "40") (name "GND") (class "Default")
      (node (ref "A40") (pin "4") (pinfunction "4_4") (pintype "passive"))
      (node (ref "B40") (pin "4") (pinfunction "4_4") (pintype "passive"))
      (node (ref "C10") (pin "2") (pinfunction "2_2") (pintype "passive"))
      (node (ref "C11") (pin "2") (pinfunction "2_2") (pintype "passive"))
      (node (ref "C12") (pin "2") (pinfunction "2_2") (pintype "passive"))
      (node (ref "C13") (pin "2") (pinfunction "2_2") (pintype "passive"))
      (node (ref "C14") (pin "2") (pinfunction "2_2") (pintype "passive"))
      (node (ref "C15") (pin "2") (pinfunction "2_2") (pintype "passive"))
      (node (ref "C16") (pin "2") (pinfunction "2_2") (pintype "passive"))
      (node (ref "C17") (pin "2") (pinfunction "2_2") (pintype "passive"))
      (node (ref "C18") (pin "2") (pinfunction "2_2") (pintype "passive"))
      (node (ref "C19") (pin "2") (pinfunction "2_2") (pintype "passive"))
      (node (ref "C20") (pin "2") (pinfunction "2_2") (pintype "passive"))
      (node (ref "C21") (pin "2") (pinfunction "2_2") (pintype "passive"))
      (node (ref "C22") (pin "2") (pinfunction "2_2") (pintype "passive"))
      (node (ref "C23") (pin "2") (pinfunction "2_2") (pintype "passive"))
      (node (ref "C24") (pin "2") (pinfunction "2_2") (pintype "passive"))
      (node (ref "C25") (pin "2") (pinfunction "2_2") (pintype "passive"))
      (node (ref "C4") (pin "2") (pinfunction "2_2") (pintype "passive"))
      (node (ref "C40") (pin "17") (pinfunction "17_17") (pintype "passive"))
      (node (ref "C40") (pin "18") (pinfunction "18_18") (pintype "passive"))
      (node (ref "C40") (pin "19") (pinfunction "19_19") (pintype "passive"))
      (node (ref "C40") (pin "20") (pinfunction "20_20") (pintype "passive"))
      (node (ref "C5") (pin "2") (pinfunction "2_2") (pintype "passive"))
      (node (ref "C6") (pin "2") (pinfunction "2_2") (pintype "passive"))
      (node (ref "C7") (pin "2") (pinfunction "2_2") (pintype "passive"))
      (node (ref "C8") (pin "2") (pinfunction "2_2") (pintype "passive"))
      (node (ref "C9") (pin "2") (pinfunction "2_2") (pintype "passive"))
      (node (ref "CONFIG") (pin "1") (pinfunction "1_1") (pintype "passive"))
      (node (ref "CONFIG") (pin "11") (pinfunction "11_11") (pintype "passive"))
      (node (ref "CONFIG") (pin "3") (pinfunction "3_3") (pintype "passive"))
      (node (ref "CONFIG") (pin "5") (pinfunction "5_5") (pintype "passive"))
      (node (ref "CONFIG") (pin "7") (pinfunction "7_7") (pintype "passive"))
      (node (ref "CONFIG") (pin "9") (pinfunction "9_9") (pintype "passive"))
      (node (ref "CONFIGSW") (pin "10") (pinfunction "10_10") (pintype "passive"))
      (node (ref "CONFIGSW") (pin "11") (pinfunction "11_11") (pintype "passive"))
      (node (ref "CONFIGSW") (pin "12") (pinfunction "12_12") (pintype "passive"))
      (node (ref "CONFIGSW") (pin "13") (pinfunction "13_13") (pintype "passive"))
      (node (ref "CONFIGSW") (pin "14") (pinfunction "14_14") (pintype "passive"))
      (node (ref "CONFIGSW") (pin "15") (pinfunction "15_15") (pintype "passive"))
      (node (ref "CONFIGSW") (pin "16") (pinfunction "16_16") (pintype "passive"))
      (node (ref "CONFIGSW") (pin "17") (pinfunction "17_17") (pintype "passive"))
      (node (ref "CONFIGSW") (pin "18") (pinfunction "18_18") (pintype "passive"))
      (node (ref "D1") (pin "A") (pinfunction "A_A") (pintype "passive"))
      (node (ref "D2") (pin "A") (pinfunction "A_A") (pintype "passive"))
      (node (ref "D40") (pin "17") (pinfunction "17_17") (pintype "passive"))
      (node (ref "D40") (pin "18") (pinfunction "18_18") (pintype "passive"))
      (node (ref "D40") (pin "19") (pinfunction "19_19") (pintype "passive"))
      (node (ref "D40") (pin "20") (pinfunction "20_20") (pintype "passive"))
      (node (ref "E40") (pin "17") (pinfunction "17_17") (pintype "passive"))
      (node (ref "E40") (pin "18") (pinfunction "18_18") (pintype "passive"))
      (node (ref "E40") (pin "19") (pinfunction "19_19") (pintype "passive"))
      (node (ref "E40") (pin "20") (pinfunction "20_20") (pintype "passive"))
      (node (ref "F40") (pin "17") (pinfunction "17_17") (pintype "passive"))
      (node (ref "F40") (pin "18") (pinfunction "18_18") (pintype "passive"))
      (node (ref "F40") (pin "19") (pinfunction "19_19") (pintype "passive"))
      (node (ref "F40") (pin "20") (pinfunction "20_20") (pintype "passive"))
      (node (ref "GND1") (pin "1") (pinfunction "1_1") (pintype "passive"))
      (node (ref "GND2") (pin "1") (pinfunction "1_1") (pintype "passive"))
      (node (ref "GND3") (pin "1") (pinfunction "1_1") (pintype "passive"))
      (node (ref "GND4") (pin "1") (pinfunction "1_1") (pintype "passive"))
      (node (ref "IC1") (pin "13") (pinfunction "G_13") (pintype "input"))
      (node (ref "IC10") (pin "13") (pinfunction "G_13") (pintype "input"))
      (node (ref "IC11") (pin "13") (pinfunction "G_13") (pintype "input"))
      (node (ref "IC12") (pin "13") (pinfunction "G_13") (pintype "input"))
      (node (ref "IC13") (pin "13") (pinfunction "G_13") (pintype "input"))
      (node (ref "IC14") (pin "10") (pinfunction "SER_10") (pintype "input"))
      (node (ref "IC14") (pin "15") (pinfunction "INH_15") (pintype "input"))
      (node (ref "IC15") (pin "15") (pinfunction "INH_15") (pintype "input"))
      (node (ref "IC16") (pin "13") (pinfunction "G_13") (pintype "input"))
      (node (ref "IC17") (pin "1") (pinfunction "G_1") (pintype "input"))
      (node (ref "IC17") (pin "19") (pinfunction "G_19") (pintype "input"))
      (node (ref "IC18") (pin "15") (pinfunction "INH_15") (pintype "input"))
      (node (ref "IC2") (pin "15") (pinfunction "INH_15") (pintype "input"))
      (node (ref "IC4") (pin "13") (pinfunction "G_13") (pintype "input"))
      (node (ref "IC5") (pin "13") (pinfunction "G_13") (pintype "input"))
      (node (ref "IC6") (pin "13") (pinfunction "G_13") (pintype "input"))
      (node (ref "IC7") (pin "13") (pinfunction "G_13") (pintype "input"))
      (node (ref "IC8") (pin "13") (pinfunction "G_13") (pintype "input"))
      (node (ref "IC9") (pin "13") (pinfunction "G_13") (pintype "input"))
      (node (ref "IDE") (pin "19") (pinfunction "19_19") (pintype "passive"))
      (node (ref "IDE") (pin "2") (pinfunction "2_2") (pintype "passive"))
      (node (ref "IDE") (pin "22") (pinfunction "22_22") (pintype "passive"))
      (node (ref "IDE") (pin "24") (pinfunction "24_24") (pintype "passive"))
      (node (ref "IDE") (pin "26") (pinfunction "26_26") (pintype "passive"))
      (node (ref "IDE") (pin "28") (pinfunction "28_28") (pintype "passive"))
      (node (ref "IDE") (pin "30") (pinfunction "30_30") (pintype "passive"))
      (node (ref "IDE") (pin "40") (pinfunction "40_40") (pintype "passive"))
      (node (ref "J1") (pin "2") (pinfunction "2_2") (pintype "passive"))
      (node (ref "J1") (pin "3") (pinfunction "3_3") (pintype "passive"))
      (node (ref "J3") (pin "2") (pinfunction "2_2") (pintype "passive"))
      (node (ref "J4") (pin "11") (pinfunction "CMN_11") (pintype "input"))
      (node (ref "LOCKSW") (pin "1") (pinfunction "1_1") (pintype "passive"))
      (node (ref "R17") (pin "1") (pinfunction "1_1") (pintype "passive"))
      (node (ref "R18") (pin "1") (pinfunction "1_1") (pintype "passive"))
      (node (ref "RESET") (pin "3") (pinfunction "P_3") (pintype "passive"))
      (node (ref "RESET") (pin "4") (pinfunction "P1_4") (pintype "passive"))
      (node (ref "RS-232") (pin "3") (pinfunction "3_3") (pintype "passive"))
      (node (ref "SLOT1") (pin "19") (pinfunction "19_19") (pintype "passive"))
      (node (ref "SLOT1") (pin "2") (pinfunction "2_2") (pintype "passive"))
      (node (ref "SLOT1") (pin "22") (pinfunction "22_22") (pintype "passive"))
      (node (ref "SLOT1") (pin "24") (pinfunction "24_24") (pintype "passive"))
      (node (ref "SLOT1") (pin "26") (pinfunction "26_26") (pintype "passive"))
      (node (ref "SLOT1") (pin "30") (pinfunction "30_30") (pintype "passive"))
      (node (ref "SLOT1") (pin "40") (pinfunction "40_40") (pintype "passive"))
      (node (ref "SLOT2") (pin "19") (pinfunction "19_19") (pintype "passive"))
      (node (ref "SLOT2") (pin "2") (pinfunction "2_2") (pintype "passive"))
      (node (ref "SLOT2") (pin "22") (pinfunction "22_22") (pintype "passive"))
      (node (ref "SLOT2") (pin "24") (pinfunction "24_24") (pintype "passive"))
      (node (ref "SLOT2") (pin "26") (pinfunction "26_26") (pintype "passive"))
      (node (ref "SLOT2") (pin "30") (pinfunction "30_30") (pintype "passive"))
      (node (ref "SLOT2") (pin "40") (pinfunction "40_40") (pintype "passive"))
      (node (ref "V-") (pin "1") (pinfunction "1_1") (pintype "passive"))
      (node (ref "X1") (pin "5") (pinfunction "F_5") (pintype "passive"))
      (node (ref "X1") (pin "G1") (pinfunction "G1_G1") (pintype "passive"))
      (node (ref "X1") (pin "G2") (pinfunction "G2_G2") (pintype "passive"))
      (node (ref "XESS") (pin "52") (pinfunction "GND_52") (pintype "power_in"))
    )
    (net (code "41") (name "I2C-SCL") (class "Default")
      (node (ref "SLOT1") (pin "27") (pinfunction "27_27") (pintype "passive"))
      (node (ref "SLOT2") (pin "27") (pinfunction "27_27") (pintype "passive"))
      (node (ref "XESS") (pin "23") (pinfunction "F5_23") (pintype "bidirectional"))
    )
    (net (code "42") (name "I2C-SDA") (class "Default")
      (node (ref "SLOT1") (pin "29") (pinfunction "29_29") (pintype "passive"))
      (node (ref "SLOT2") (pin "29") (pinfunction "29_29") (pintype "passive"))
      (node (ref "XESS") (pin "24") (pinfunction "D2_24") (pintype "bidirectional"))
    )
    (net (code "43") (name "IDE-CS0#") (class "Default")
      (node (ref "IDE") (pin "37") (pinfunction "37_37") (pintype "passive"))
      (node (ref "XESS") (pin "7") (pinfunction "G15_7") (pintype "bidirectional"))
    )
    (net (code "44") (name "IDE-CS1#") (class "Default")
      (node (ref "IDE") (pin "38") (pinfunction "38_38") (pintype "passive"))
      (node (ref "XESS") (pin "8") (pinfunction "G14_8") (pintype "bidirectional"))
    )
    (net (code "45") (name "IDE-DMACK#") (class "Default")
      (node (ref "IDE") (pin "29") (pinfunction "29_29") (pintype "passive"))
      (node (ref "XESS") (pin "43") (pinfunction "K1_43") (pintype "bidirectional"))
    )
    (net (code "46") (name "IDE-DMARQ") (class "Default")
      (node (ref "R12") (pin "1") (pinfunction "1_1") (pintype "passive"))
      (node (ref "R17") (pin "2") (pinfunction "2_2") (pintype "passive"))
      (node (ref "XESS") (pin "49") (pinfunction "L4_49") (pintype "bidirectional"))
    )
    (net (code "47") (name "IDE-IORDY") (class "Default")
      (node (ref "R15") (pin "1") (pinfunction "1_1") (pintype "passive"))
      (node (ref "R19") (pin "1") (pinfunction "1_1") (pintype "passive"))
      (node (ref "XESS") (pin "44") (pinfunction "L2_44") (pintype "bidirectional"))
    )
    (net (code "48") (name "IDE-IRQ") (class "Default")
      (node (ref "R16") (pin "1") (pinfunction "1_1") (pintype "passive"))
      (node (ref "R18") (pin "2") (pinfunction "2_2") (pintype "passive"))
      (node (ref "XESS") (pin "3") (pinfunction "H15_3") (pintype "bidirectional"))
    )
    (net (code "49") (name "IF0") (class "Default")
      (node (ref "C40") (pin "24") (pinfunction "24_24") (pintype "passive"))
      (node (ref "IC1") (pin "6") (pinfunction "QG_6") (pintype "tri_state"))
    )
    (net (code "50") (name "IF1") (class "Default")
      (node (ref "C40") (pin "25") (pinfunction "25_25") (pintype "passive"))
      (node (ref "IC4") (pin "15") (pinfunction "QA_15") (pintype "tri_state"))
    )
    (net (code "51") (name "IF2") (class "Default")
      (node (ref "C40") (pin "34") (pinfunction "34_34") (pintype "passive"))
      (node (ref "IC4") (pin "2") (pinfunction "QC_2") (pintype "tri_state"))
    )
    (net (code "52") (name "ION") (class "Default")
      (node (ref "D40") (pin "34") (pinfunction "34_34") (pintype "passive"))
      (node (ref "IC16") (pin "3") (pinfunction "QD_3") (pintype "tri_state"))
    )
    (net (code "53") (name "IOT") (class "Default")
      (node (ref "D40") (pin "23") (pinfunction "23_23") (pintype "passive"))
      (node (ref "IC13") (pin "4") (pinfunction "QE_4") (pintype "tri_state"))
    )
    (net (code "54") (name "ISZ") (class "Default")
      (node (ref "D40") (pin "6") (pinfunction "6_6") (pintype "passive"))
      (node (ref "IC13") (pin "1") (pinfunction "QB_1") (pintype "tri_state"))
    )
    (net (code "55") (name "JMP") (class "Default")
      (node (ref "D40") (pin "12") (pinfunction "12_12") (pintype "passive"))
      (node (ref "IC16") (pin "15") (pinfunction "QA_15") (pintype "tri_state"))
    )
    (net (code "56") (name "JMS") (class "Default")
      (node (ref "D40") (pin "10") (pinfunction "10_10") (pintype "passive"))
      (node (ref "IC12") (pin "7") (pinfunction "QH_7") (pintype "tri_state"))
    )
    (net (code "57") (name "LA") (class "Default")
      (node (ref "B40") (pin "18") (pinfunction "18_18") (pintype "passive"))
      (node (ref "IC2") (pin "14") (pinfunction "D_14") (pintype "input"))
      (node (ref "R43") (pin "1") (pinfunction "1_1") (pintype "passive"))
    )
    (net (code "58") (name "LEFT") (class "Default")
      (node (ref "IC8") (pin "9") (pinfunction "QH*_9") (pintype "tri_state"))
      (node (ref "IC9") (pin "14") (pinfunction "SER_14") (pintype "input"))
      (node (ref "SV1") (pin "1") (pinfunction "1_1") (pintype "passive"))
      (node (ref "SV2") (pin "1") (pinfunction "1_1") (pintype "passive"))
    )
    (net (code "59") (name "LINK") (class "Default")
      (node (ref "C40") (pin "28") (pinfunction "28_28") (pintype "passive"))
      (node (ref "IC4") (pin "3") (pinfunction "QD_3") (pintype "tri_state"))
    )
    (net (code "60") (name "LSCK") (class "Default")
      (node (ref "IC1") (pin "11") (pinfunction "SCK_11") (pintype "input"))
      (node (ref "IC10") (pin "11") (pinfunction "SCK_11") (pintype "input"))
      (node (ref "IC11") (pin "11") (pinfunction "SCK_11") (pintype "input"))
      (node (ref "IC12") (pin "11") (pinfunction "SCK_11") (pintype "input"))
      (node (ref "IC13") (pin "11") (pinfunction "SCK_11") (pintype "input"))
      (node (ref "IC16") (pin "11") (pinfunction "SCK_11") (pintype "input"))
      (node (ref "IC17") (pin "14") (pinfunction "Y3_14") (pintype "tri_state"))
      (node (ref "IC17") (pin "16") (pinfunction "Y2_16") (pintype "tri_state"))
      (node (ref "IC19") (pin "1") (pinfunction "I0_1") (pintype "input"))
      (node (ref "IC19") (pin "2") (pinfunction "I1_2") (pintype "input"))
      (node (ref "IC4") (pin "11") (pinfunction "SCK_11") (pintype "input"))
      (node (ref "IC5") (pin "11") (pinfunction "SCK_11") (pintype "input"))
      (node (ref "IC6") (pin "11") (pinfunction "SCK_11") (pintype "input"))
      (node (ref "IC7") (pin "11") (pinfunction "SCK_11") (pintype "input"))
      (node (ref "IC8") (pin "11") (pinfunction "SCK_11") (pintype "input"))
      (node (ref "IC9") (pin "11") (pinfunction "SCK_11") (pintype "input"))
      (node (ref "SV1") (pin "3") (pinfunction "3_3") (pintype "passive"))
      (node (ref "SV2") (pin "3") (pinfunction "3_3") (pintype "passive"))
    )
    (net (code "61") (name "LSER") (class "Default")
      (node (ref "IC1") (pin "14") (pinfunction "SER_14") (pintype "input"))
      (node (ref "IC17") (pin "18") (pinfunction "Y1_18") (pintype "tri_state"))
      (node (ref "SV1") (pin "9") (pinfunction "9_9") (pintype "passive"))
      (node (ref "SV2") (pin "9") (pinfunction "9_9") (pintype "passive"))
    )
    (net (code "62") (name "MA0") (class "Default")
      (node (ref "E40") (pin "3") (pinfunction "3_3") (pintype "passive"))
      (node (ref "IC5") (pin "1") (pinfunction "QB_1") (pintype "tri_state"))
    )
    (net (code "63") (name "MA1") (class "Default")
      (node (ref "E40") (pin "8") (pinfunction "8_8") (pintype "passive"))
      (node (ref "IC5") (pin "6") (pinfunction "QG_6") (pintype "tri_state"))
    )
    (net (code "64") (name "MA2") (class "Default")
      (node (ref "E40") (pin "13") (pinfunction "13_13") (pintype "passive"))
      (node (ref "IC6") (pin "3") (pinfunction "QD_3") (pintype "tri_state"))
    )
    (net (code "65") (name "MA3") (class "Default")
      (node (ref "E40") (pin "22") (pinfunction "22_22") (pintype "passive"))
      (node (ref "IC7") (pin "15") (pinfunction "QA_15") (pintype "tri_state"))
    )
    (net (code "66") (name "MA4") (class "Default")
      (node (ref "E40") (pin "27") (pinfunction "27_27") (pintype "passive"))
      (node (ref "IC7") (pin "5") (pinfunction "QF_5") (pintype "tri_state"))
    )
    (net (code "67") (name "MA5") (class "Default")
      (node (ref "E40") (pin "32") (pinfunction "32_32") (pintype "passive"))
      (node (ref "IC8") (pin "2") (pinfunction "QC_2") (pintype "tri_state"))
    )
    (net (code "68") (name "MA6") (class "Default")
      (node (ref "F40") (pin "3") (pinfunction "3_3") (pintype "passive"))
      (node (ref "IC9") (pin "1") (pinfunction "QB_1") (pintype "tri_state"))
    )
    (net (code "69") (name "MA7") (class "Default")
      (node (ref "F40") (pin "8") (pinfunction "8_8") (pintype "passive"))
      (node (ref "IC9") (pin "6") (pinfunction "QG_6") (pintype "tri_state"))
    )
    (net (code "70") (name "MA8") (class "Default")
      (node (ref "F40") (pin "13") (pinfunction "13_13") (pintype "passive"))
      (node (ref "IC10") (pin "3") (pinfunction "QD_3") (pintype "tri_state"))
    )
    (net (code "71") (name "MA9") (class "Default")
      (node (ref "F40") (pin "22") (pinfunction "22_22") (pintype "passive"))
      (node (ref "IC11") (pin "15") (pinfunction "QA_15") (pintype "tri_state"))
    )
    (net (code "72") (name "MA10") (class "Default")
      (node (ref "F40") (pin "27") (pinfunction "27_27") (pintype "passive"))
      (node (ref "IC11") (pin "5") (pinfunction "QF_5") (pintype "tri_state"))
    )
    (net (code "73") (name "MA11") (class "Default")
      (node (ref "F40") (pin "32") (pinfunction "32_32") (pintype "passive"))
      (node (ref "IC12") (pin "2") (pinfunction "QC_2") (pintype "tri_state"))
    )
    (net (code "74") (name "MASTER-RESET#") (class "Default")
      (node (ref "IC17") (pin "3") (pinfunction "Y4_3") (pintype "tri_state"))
      (node (ref "IDE") (pin "1") (pinfunction "1_1") (pintype "passive"))
      (node (ref "SLOT1") (pin "1") (pinfunction "1_1") (pintype "passive"))
      (node (ref "SLOT2") (pin "1") (pinfunction "1_1") (pintype "passive"))
    )
    (net (code "75") (name "MB0") (class "Default")
      (node (ref "E40") (pin "5") (pinfunction "5_5") (pintype "passive"))
      (node (ref "IC5") (pin "2") (pinfunction "QC_2") (pintype "tri_state"))
    )
    (net (code "76") (name "MB1") (class "Default")
      (node (ref "E40") (pin "6") (pinfunction "6_6") (pintype "passive"))
      (node (ref "IC5") (pin "7") (pinfunction "QH_7") (pintype "tri_state"))
    )
    (net (code "77") (name "MB2") (class "Default")
      (node (ref "E40") (pin "15") (pinfunction "15_15") (pintype "passive"))
      (node (ref "IC6") (pin "4") (pinfunction "QE_4") (pintype "tri_state"))
    )
    (net (code "78") (name "MB3") (class "Default")
      (node (ref "E40") (pin "16") (pinfunction "16_16") (pintype "passive"))
      (node (ref "IC7") (pin "1") (pinfunction "QB_1") (pintype "tri_state"))
    )
    (net (code "79") (name "MB4") (class "Default")
      (node (ref "E40") (pin "29") (pinfunction "29_29") (pintype "passive"))
      (node (ref "IC7") (pin "6") (pinfunction "QG_6") (pintype "tri_state"))
    )
    (net (code "80") (name "MB5") (class "Default")
      (node (ref "E40") (pin "30") (pinfunction "30_30") (pintype "passive"))
      (node (ref "IC8") (pin "3") (pinfunction "QD_3") (pintype "tri_state"))
    )
    (net (code "81") (name "MB6") (class "Default")
      (node (ref "F40") (pin "5") (pinfunction "5_5") (pintype "passive"))
      (node (ref "IC9") (pin "2") (pinfunction "QC_2") (pintype "tri_state"))
    )
    (net (code "82") (name "MB7") (class "Default")
      (node (ref "F40") (pin "6") (pinfunction "6_6") (pintype "passive"))
      (node (ref "IC9") (pin "7") (pinfunction "QH_7") (pintype "tri_state"))
    )
    (net (code "83") (name "MB8") (class "Default")
      (node (ref "F40") (pin "15") (pinfunction "15_15") (pintype "passive"))
      (node (ref "IC10") (pin "4") (pinfunction "QE_4") (pintype "tri_state"))
    )
    (net (code "84") (name "MB9") (class "Default")
      (node (ref "F40") (pin "16") (pinfunction "16_16") (pintype "passive"))
      (node (ref "IC11") (pin "1") (pinfunction "QB_1") (pintype "tri_state"))
    )
    (net (code "85") (name "MB10") (class "Default")
      (node (ref "F40") (pin "29") (pinfunction "29_29") (pintype "passive"))
      (node (ref "IC11") (pin "6") (pinfunction "QG_6") (pintype "tri_state"))
    )
    (net (code "86") (name "MB11") (class "Default")
      (node (ref "F40") (pin "30") (pinfunction "30_30") (pintype "passive"))
      (node (ref "IC12") (pin "3") (pinfunction "QD_3") (pintype "tri_state"))
    )
    (net (code "87") (name "MQ0") (class "Default")
      (node (ref "E40") (pin "9") (pinfunction "9_9") (pintype "passive"))
      (node (ref "IC5") (pin "4") (pinfunction "QE_4") (pintype "tri_state"))
    )
    (net (code "88") (name "MQ1") (class "Default")
      (node (ref "E40") (pin "2") (pinfunction "2_2") (pintype "passive"))
      (node (ref "IC6") (pin "1") (pinfunction "QB_1") (pintype "tri_state"))
    )
    (net (code "89") (name "MQ2") (class "Default")
      (node (ref "E40") (pin "23") (pinfunction "23_23") (pintype "passive"))
      (node (ref "IC6") (pin "6") (pinfunction "QG_6") (pintype "tri_state"))
    )
    (net (code "90") (name "MQ3") (class "Default")
      (node (ref "E40") (pin "12") (pinfunction "12_12") (pintype "passive"))
      (node (ref "IC7") (pin "3") (pinfunction "QD_3") (pintype "tri_state"))
    )
    (net (code "91") (name "MQ4") (class "Default")
      (node (ref "E40") (pin "33") (pinfunction "33_33") (pintype "passive"))
      (node (ref "IC8") (pin "15") (pinfunction "QA_15") (pintype "tri_state"))
    )
    (net (code "92") (name "MQ5") (class "Default")
      (node (ref "E40") (pin "26") (pinfunction "26_26") (pintype "passive"))
      (node (ref "IC8") (pin "5") (pinfunction "QF_5") (pintype "tri_state"))
    )
    (net (code "93") (name "MQ6") (class "Default")
      (node (ref "F40") (pin "9") (pinfunction "9_9") (pintype "passive"))
      (node (ref "IC9") (pin "4") (pinfunction "QE_4") (pintype "tri_state"))
    )
    (net (code "94") (name "MQ7") (class "Default")
      (node (ref "F40") (pin "2") (pinfunction "2_2") (pintype "passive"))
      (node (ref "IC10") (pin "1") (pinfunction "QB_1") (pintype "tri_state"))
    )
    (net (code "95") (name "MQ8") (class "Default")
      (node (ref "F40") (pin "23") (pinfunction "23_23") (pintype "passive"))
      (node (ref "IC10") (pin "6") (pinfunction "QG_6") (pintype "tri_state"))
    )
    (net (code "96") (name "MQ9") (class "Default")
      (node (ref "F40") (pin "12") (pinfunction "12_12") (pintype "passive"))
      (node (ref "IC11") (pin "3") (pinfunction "QD_3") (pintype "tri_state"))
    )
    (net (code "97") (name "MQ10") (class "Default")
      (node (ref "F40") (pin "33") (pinfunction "33_33") (pintype "passive"))
      (node (ref "IC12") (pin "15") (pinfunction "QA_15") (pintype "tri_state"))
    )
    (net (code "98") (name "MQ11") (class "Default")
      (node (ref "F40") (pin "26") (pinfunction "26_26") (pintype "passive"))
      (node (ref "IC12") (pin "5") (pinfunction "QF_5") (pintype "tri_state"))
    )
    (net (code "99") (name "Net-(+12V-Pad1)") (class "Default")
      (node (ref "+12V") (pin "1") (pinfunction "1_1") (pintype "passive"))
      (node (ref "J1") (pin "1") (pinfunction "1_1") (pintype "passive"))
    )
    (net (code "100") (name "Net-(IC1A-QH*)") (class "Default")
      (node (ref "IC1") (pin "9") (pinfunction "QH*_9") (pintype "tri_state"))
      (node (ref "IC4") (pin "14") (pinfunction "SER_14") (pintype "input"))
    )
    (net (code "101") (name "Net-(IC3A-C1+)") (class "Default")
      (node (ref "C2") (pin "1") (pinfunction "1_1") (pintype "passive"))
      (node (ref "IC3") (pin "1") (pinfunction "C1+_1") (pintype "bidirectional"))
    )
    (net (code "102") (name "Net-(IC3A-C1-)") (class "Default")
      (node (ref "C2") (pin "2") (pinfunction "2_2") (pintype "passive"))
      (node (ref "IC3") (pin "3") (pinfunction "C1-_3") (pintype "bidirectional"))
    )
    (net (code "103") (name "Net-(IC3A-C2+)") (class "Default")
      (node (ref "C3") (pin "1") (pinfunction "1_1") (pintype "passive"))
      (node (ref "IC3") (pin "4") (pinfunction "C2+_4") (pintype "bidirectional"))
    )
    (net (code "104") (name "Net-(IC3A-C2-)") (class "Default")
      (node (ref "C3") (pin "2") (pinfunction "2_2") (pintype "passive"))
      (node (ref "IC3") (pin "5") (pinfunction "C2-_5") (pintype "bidirectional"))
    )
    (net (code "105") (name "Net-(IC3A-R2OUT)") (class "Default")
      (node (ref "IC3") (pin "9") (pinfunction "R2OUT_9") (pintype "output"))
      (node (ref "R2") (pin "2") (pinfunction "2_2") (pintype "passive"))
    )
    (net (code "106") (name "Net-(IC3A-T1IN)") (class "Default")
      (node (ref "IC3") (pin "11") (pinfunction "T1IN_11") (pintype "input"))
      (node (ref "R1") (pin "2") (pinfunction "2_2") (pintype "passive"))
    )
    (net (code "107") (name "Net-(IC3A-T2IN)") (class "Default")
      (node (ref "IC3") (pin "10") (pinfunction "T2IN_10") (pintype "input"))
      (node (ref "R3") (pin "2") (pinfunction "2_2") (pintype "passive"))
    )
    (net (code "108") (name "Net-(IC3A-V+)") (class "Default")
      (node (ref "C1") (pin "2") (pinfunction "2_2") (pintype "passive"))
      (node (ref "IC3") (pin "2") (pinfunction "V+_2") (pintype "bidirectional"))
    )
    (net (code "109") (name "Net-(IC3A-V-)") (class "Default")
      (node (ref "C4") (pin "1") (pinfunction "1_1") (pintype "passive"))
      (node (ref "IC3") (pin "6") (pinfunction "V-_6") (pintype "bidirectional"))
    )
    (net (code "110") (name "Net-(IC4A-QH*)") (class "Default")
      (node (ref "IC4") (pin "9") (pinfunction "QH*_9") (pintype "tri_state"))
      (node (ref "IC5") (pin "14") (pinfunction "SER_14") (pintype "input"))
    )
    (net (code "111") (name "Net-(IC5A-QH*)") (class "Default")
      (node (ref "IC5") (pin "9") (pinfunction "QH*_9") (pintype "tri_state"))
      (node (ref "IC6") (pin "14") (pinfunction "SER_14") (pintype "input"))
    )
    (net (code "112") (name "Net-(IC6A-QH*)") (class "Default")
      (node (ref "IC6") (pin "9") (pinfunction "QH*_9") (pintype "tri_state"))
      (node (ref "IC7") (pin "14") (pinfunction "SER_14") (pintype "input"))
    )
    (net (code "113") (name "Net-(IC7A-QH*)") (class "Default")
      (node (ref "IC7") (pin "9") (pinfunction "QH*_9") (pintype "tri_state"))
      (node (ref "IC8") (pin "14") (pinfunction "SER_14") (pintype "input"))
    )
    (net (code "114") (name "Net-(IC10A-QH*)") (class "Default")
      (node (ref "IC10") (pin "9") (pinfunction "QH*_9") (pintype "tri_state"))
      (node (ref "IC11") (pin "14") (pinfunction "SER_14") (pintype "input"))
    )
    (net (code "115") (name "Net-(IC10A-SER)") (class "Default")
      (node (ref "IC10") (pin "14") (pinfunction "SER_14") (pintype "input"))
      (node (ref "IC9") (pin "9") (pinfunction "QH*_9") (pintype "tri_state"))
    )
    (net (code "116") (name "Net-(IC11A-QH*)") (class "Default")
      (node (ref "IC11") (pin "9") (pinfunction "QH*_9") (pintype "tri_state"))
      (node (ref "IC12") (pin "14") (pinfunction "SER_14") (pintype "input"))
    )
    (net (code "117") (name "Net-(IC12A-QH*)") (class "Default")
      (node (ref "IC12") (pin "9") (pinfunction "QH*_9") (pintype "tri_state"))
      (node (ref "IC13") (pin "14") (pinfunction "SER_14") (pintype "input"))
    )
    (net (code "118") (name "Net-(IC13A-QH*)") (class "Default")
      (node (ref "IC13") (pin "9") (pinfunction "QH*_9") (pintype "tri_state"))
      (node (ref "IC16") (pin "14") (pinfunction "SER_14") (pintype "input"))
    )
    (net (code "119") (name "Net-(IC14A-QH)") (class "Default")
      (node (ref "IC14") (pin "9") (pinfunction "QH_9") (pintype "output"))
      (node (ref "IC15") (pin "10") (pinfunction "SER_10") (pintype "input"))
    )
    (net (code "120") (name "Net-(IC15A-QH)") (class "Default")
      (node (ref "IC15") (pin "9") (pinfunction "QH_9") (pintype "output"))
      (node (ref "IC2") (pin "10") (pinfunction "SER_10") (pintype "input"))
    )
    (net (code "121") (name "Net-(IC16A-QH*)") (class "Default")
      (node (ref "IC16") (pin "9") (pinfunction "QH*_9") (pintype "tri_state"))
      (node (ref "IC19") (pin "5") (pinfunction "I1_5") (pintype "input"))
    )
    (net (code "122") (name "Net-(IC17B-A4)") (class "Default")
      (node (ref "C5") (pin "1") (pinfunction "1_1") (pintype "passive"))
      (node (ref "IC17") (pin "17") (pinfunction "A4_17") (pintype "input"))
      (node (ref "R20") (pin "2") (pinfunction "2_2") (pintype "passive"))
      (node (ref "R23") (pin "2") (pinfunction "2_2") (pintype "passive"))
      (node (ref "RESET") (pin "1") (pinfunction "S_1") (pintype "passive"))
      (node (ref "RESET") (pin "2") (pinfunction "S1_2") (pintype "passive"))
    )
    (net (code "123") (name "Net-(IC17B-Y2)") (class "Default")
      (node (ref "IC17") (pin "7") (pinfunction "Y2_7") (pintype "tri_state"))
      (node (ref "R11") (pin "1") (pinfunction "1_1") (pintype "passive"))
    )
    (net (code "124") (name "Net-(IC18A-SER)") (class "Default")
      (node (ref "IC18") (pin "10") (pinfunction "SER_10") (pintype "input"))
      (node (ref "IC2") (pin "9") (pinfunction "QH_9") (pintype "output"))
    )
    (net (code "125") (name "Net-(IC19A-O)") (class "Default")
      (node (ref "IC19") (pin "3") (pinfunction "O_3") (pintype "output"))
      (node (ref "IC19") (pin "4") (pinfunction "I0_4") (pintype "input"))
    )
    (net (code "126") (name "Net-(IDE-Pad21)") (class "Default")
      (node (ref "IDE") (pin "21") (pinfunction "21_21") (pintype "passive"))
      (node (ref "R12") (pin "2") (pinfunction "2_2") (pintype "passive"))
    )
    (net (code "127") (name "Net-(IDE-Pad23)") (class "Default")
      (node (ref "IDE") (pin "23") (pinfunction "23_23") (pintype "passive"))
      (node (ref "R13") (pin "2") (pinfunction "2_2") (pintype "passive"))
    )
    (net (code "128") (name "Net-(IDE-Pad25)") (class "Default")
      (node (ref "IDE") (pin "25") (pinfunction "25_25") (pintype "passive"))
      (node (ref "R14") (pin "2") (pinfunction "2_2") (pintype "passive"))
    )
    (net (code "129") (name "Net-(IDE-Pad27)") (class "Default")
      (node (ref "IDE") (pin "27") (pinfunction "27_27") (pintype "passive"))
      (node (ref "R15") (pin "2") (pinfunction "2_2") (pintype "passive"))
    )
    (net (code "130") (name "Net-(IDE-Pad31)") (class "Default")
      (node (ref "IDE") (pin "31") (pinfunction "31_31") (pintype "passive"))
      (node (ref "R16") (pin "2") (pinfunction "2_2") (pintype "passive"))
    )
    (net (code "131") (name "Net-(R21-Pad2)") (class "Default")
      (node (ref "R21") (pin "2") (pinfunction "2_2") (pintype "passive"))
      (node (ref "SLOT1") (pin "31") (pinfunction "31_31") (pintype "passive"))
    )
    (net (code "132") (name "Net-(R22-Pad2)") (class "Default")
      (node (ref "R22") (pin "2") (pinfunction "2_2") (pintype "passive"))
      (node (ref "SLOT2") (pin "31") (pinfunction "31_31") (pintype "passive"))
    )
    (net (code "133") (name "OPR") (class "Default")
      (node (ref "D40") (pin "16") (pinfunction "16_16") (pintype "passive"))
      (node (ref "IC13") (pin "7") (pinfunction "QH_7") (pintype "tri_state"))
    )
    (net (code "134") (name "PAUSE") (class "Default")
      (node (ref "D40") (pin "31") (pinfunction "31_31") (pintype "passive"))
      (node (ref "IC16") (pin "1") (pinfunction "QB_1") (pintype "tri_state"))
    )
    (net (code "135") (name "PB-A0") (class "Default")
      (node (ref "IDE") (pin "35") (pinfunction "35_35") (pintype "passive"))
      (node (ref "SLOT1") (pin "35") (pinfunction "35_35") (pintype "passive"))
      (node (ref "SLOT2") (pin "35") (pinfunction "35_35") (pintype "passive"))
      (node (ref "XESS") (pin "57") (pinfunction "L5_57") (pintype "bidirectional"))
    )
    (net (code "136") (name "PB-A1") (class "Default")
      (node (ref "IDE") (pin "33") (pinfunction "33_33") (pintype "passive"))
      (node (ref "SLOT1") (pin "33") (pinfunction "33_33") (pintype "passive"))
      (node (ref "SLOT2") (pin "33") (pinfunction "33_33") (pintype "passive"))
      (node (ref "XESS") (pin "56") (pinfunction "N2_56") (pintype "bidirectional"))
    )
    (net (code "137") (name "PB-A2") (class "Default")
      (node (ref "IDE") (pin "36") (pinfunction "36_36") (pintype "passive"))
      (node (ref "SLOT1") (pin "36") (pinfunction "36_36") (pintype "passive"))
      (node (ref "SLOT2") (pin "36") (pinfunction "36_36") (pintype "passive"))
      (node (ref "XESS") (pin "51") (pinfunction "M3_51") (pintype "bidirectional"))
    )
    (net (code "138") (name "PB-A3") (class "Default")
      (node (ref "SLOT1") (pin "38") (pinfunction "38_38") (pintype "passive"))
      (node (ref "SLOT2") (pin "38") (pinfunction "38_38") (pintype "passive"))
      (node (ref "XESS") (pin "50") (pinfunction "N1_50") (pintype "bidirectional"))
    )
    (net (code "139") (name "PB-A4") (class "Default")
      (node (ref "SLOT1") (pin "39") (pinfunction "39_39") (pintype "passive"))
      (node (ref "SLOT2") (pin "39") (pinfunction "39_39") (pintype "passive"))
      (node (ref "XESS") (pin "70") (pinfunction "T13_70") (pintype "bidirectional"))
    )
    (net (code "140") (name "PB-D0") (class "Default")
      (node (ref "IDE") (pin "17") (pinfunction "17_17") (pintype "passive"))
      (node (ref "SLOT1") (pin "17") (pinfunction "17_17") (pintype "passive"))
      (node (ref "SLOT2") (pin "17") (pinfunction "17_17") (pintype "passive"))
      (node (ref "XESS") (pin "71") (pinfunction "P12_71") (pintype "bidirectional"))
    )
    (net (code "141") (name "PB-D1") (class "Default")
      (node (ref "IDE") (pin "15") (pinfunction "15_15") (pintype "passive"))
      (node (ref "SLOT1") (pin "15") (pinfunction "15_15") (pintype "passive"))
      (node (ref "SLOT2") (pin "15") (pinfunction "15_15") (pintype "passive"))
      (node (ref "XESS") (pin "40") (pinfunction "J1_40") (pintype "bidirectional"))
    )
    (net (code "142") (name "PB-D2") (class "Default")
      (node (ref "IDE") (pin "13") (pinfunction "13_13") (pintype "passive"))
      (node (ref "SLOT1") (pin "13") (pinfunction "13_13") (pintype "passive"))
      (node (ref "SLOT2") (pin "13") (pinfunction "13_13") (pintype "passive"))
      (node (ref "XESS") (pin "39") (pinfunction "H1_39") (pintype "bidirectional"))
    )
    (net (code "143") (name "PB-D3") (class "Default")
      (node (ref "IDE") (pin "11") (pinfunction "11_11") (pintype "passive"))
      (node (ref "SLOT1") (pin "11") (pinfunction "11_11") (pintype "passive"))
      (node (ref "SLOT2") (pin "11") (pinfunction "11_11") (pintype "passive"))
      (node (ref "XESS") (pin "38") (pinfunction "H3_38") (pintype "bidirectional"))
    )
    (net (code "144") (name "PB-D4") (class "Default")
      (node (ref "IDE") (pin "9") (pinfunction "9_9") (pintype "passive"))
      (node (ref "SLOT1") (pin "9") (pinfunction "9_9") (pintype "passive"))
      (node (ref "SLOT2") (pin "9") (pinfunction "9_9") (pintype "passive"))
      (node (ref "XESS") (pin "35") (pinfunction "G2_35") (pintype "bidirectional"))
    )
    (net (code "145") (name "PB-D5") (class "Default")
      (node (ref "IDE") (pin "7") (pinfunction "7_7") (pintype "passive"))
      (node (ref "SLOT1") (pin "7") (pinfunction "7_7") (pintype "passive"))
      (node (ref "SLOT2") (pin "7") (pinfunction "7_7") (pintype "passive"))
      (node (ref "XESS") (pin "80") (pinfunction "K15_80") (pintype "bidirectional"))
    )
    (net (code "146") (name "PB-D6") (class "Default")
      (node (ref "IDE") (pin "5") (pinfunction "5_5") (pintype "passive"))
      (node (ref "SLOT1") (pin "5") (pinfunction "5_5") (pintype "passive"))
      (node (ref "SLOT2") (pin "5") (pinfunction "5_5") (pintype "passive"))
      (node (ref "XESS") (pin "81") (pinfunction "K16_81") (pintype "bidirectional"))
    )
    (net (code "147") (name "PB-D7") (class "Default")
      (node (ref "IDE") (pin "3") (pinfunction "3_3") (pintype "passive"))
      (node (ref "SLOT1") (pin "3") (pinfunction "3_3") (pintype "passive"))
      (node (ref "SLOT2") (pin "3") (pinfunction "3_3") (pintype "passive"))
      (node (ref "XESS") (pin "10") (pinfunction "F15_10") (pintype "bidirectional"))
    )
    (net (code "148") (name "PB-D8") (class "Default")
      (node (ref "IDE") (pin "4") (pinfunction "4_4") (pintype "passive"))
      (node (ref "SLOT1") (pin "4") (pinfunction "4_4") (pintype "passive"))
      (node (ref "SLOT2") (pin "4") (pinfunction "4_4") (pintype "passive"))
      (node (ref "XESS") (pin "27") (pinfunction "E2_27") (pintype "bidirectional"))
    )
    (net (code "149") (name "PB-D9") (class "Default")
      (node (ref "IDE") (pin "6") (pinfunction "6_6") (pintype "passive"))
      (node (ref "SLOT1") (pin "6") (pinfunction "6_6") (pintype "passive"))
      (node (ref "SLOT2") (pin "6") (pinfunction "6_6") (pintype "passive"))
      (node (ref "XESS") (pin "28") (pinfunction "E1_28") (pintype "bidirectional"))
    )
    (net (code "150") (name "PB-D10") (class "Default")
      (node (ref "IDE") (pin "8") (pinfunction "8_8") (pintype "passive"))
      (node (ref "SLOT1") (pin "8") (pinfunction "8_8") (pintype "passive"))
      (node (ref "SLOT2") (pin "8") (pinfunction "8_8") (pintype "passive"))
      (node (ref "XESS") (pin "29") (pinfunction "F3_29") (pintype "bidirectional"))
    )
    (net (code "151") (name "PB-D11") (class "Default")
      (node (ref "IDE") (pin "10") (pinfunction "10_10") (pintype "passive"))
      (node (ref "SLOT1") (pin "10") (pinfunction "10_10") (pintype "passive"))
      (node (ref "SLOT2") (pin "10") (pinfunction "10_10") (pintype "passive"))
      (node (ref "XESS") (pin "32") (pinfunction "F2_32") (pintype "bidirectional"))
    )
    (net (code "152") (name "PB-D12") (class "Default")
      (node (ref "IDE") (pin "12") (pinfunction "12_12") (pintype "passive"))
      (node (ref "SLOT1") (pin "12") (pinfunction "12_12") (pintype "passive"))
      (node (ref "SLOT2") (pin "12") (pinfunction "12_12") (pintype "passive"))
      (node (ref "XESS") (pin "33") (pinfunction "G4_33") (pintype "bidirectional"))
    )
    (net (code "153") (name "PB-D13") (class "Default")
      (node (ref "IDE") (pin "14") (pinfunction "14_14") (pintype "passive"))
      (node (ref "SLOT1") (pin "14") (pinfunction "14_14") (pintype "passive"))
      (node (ref "SLOT2") (pin "14") (pinfunction "14_14") (pintype "passive"))
      (node (ref "XESS") (pin "34") (pinfunction "G3_34") (pintype "bidirectional"))
    )
    (net (code "154") (name "PB-D14") (class "Default")
      (node (ref "IDE") (pin "16") (pinfunction "16_16") (pintype "passive"))
      (node (ref "SLOT1") (pin "16") (pinfunction "16_16") (pintype "passive"))
      (node (ref "SLOT2") (pin "16") (pinfunction "16_16") (pintype "passive"))
      (node (ref "XESS") (pin "36") (pinfunction "G1_36") (pintype "bidirectional"))
    )
    (net (code "155") (name "PB-D15") (class "Default")
      (node (ref "IDE") (pin "18") (pinfunction "18_18") (pintype "passive"))
      (node (ref "SLOT1") (pin "18") (pinfunction "18_18") (pintype "passive"))
      (node (ref "SLOT2") (pin "18") (pinfunction "18_18") (pintype "passive"))
      (node (ref "XESS") (pin "37") (pinfunction "H4_37") (pintype "bidirectional"))
    )
    (net (code "156") (name "PB-RD#") (class "Default")
      (node (ref "R14") (pin "1") (pinfunction "1_1") (pintype "passive"))
      (node (ref "SLOT1") (pin "25") (pinfunction "25_25") (pintype "passive"))
      (node (ref "SLOT2") (pin "25") (pinfunction "25_25") (pintype "passive"))
      (node (ref "XESS") (pin "61") (pinfunction "P2_61") (pintype "bidirectional"))
    )
    (net (code "157") (name "PB-WR#") (class "Default")
      (node (ref "R13") (pin "1") (pinfunction "1_1") (pintype "passive"))
      (node (ref "SLOT1") (pin "23") (pinfunction "23_23") (pintype "passive"))
      (node (ref "SLOT2") (pin "23") (pinfunction "23_23") (pintype "passive"))
      (node (ref "XESS") (pin "62") (pinfunction "R1_62") (pintype "bidirectional"))
    )
    (net (code "158") (name "PC0") (class "Default")
      (node (ref "E40") (pin "1") (pinfunction "1_1") (pintype "passive"))
      (node (ref "IC5") (pin "15") (pinfunction "QA_15") (pintype "tri_state"))
    )
    (net (code "159") (name "PC1") (class "Default")
      (node (ref "E40") (pin "10") (pinfunction "10_10") (pintype "passive"))
      (node (ref "IC5") (pin "5") (pinfunction "QF_5") (pintype "tri_state"))
    )
    (net (code "160") (name "PC2") (class "Default")
      (node (ref "E40") (pin "11") (pinfunction "11_11") (pintype "passive"))
      (node (ref "IC6") (pin "2") (pinfunction "QC_2") (pintype "tri_state"))
    )
    (net (code "161") (name "PC3") (class "Default")
      (node (ref "E40") (pin "24") (pinfunction "24_24") (pintype "passive"))
      (node (ref "IC6") (pin "7") (pinfunction "QH_7") (pintype "tri_state"))
    )
    (net (code "162") (name "PC4") (class "Default")
      (node (ref "E40") (pin "25") (pinfunction "25_25") (pintype "passive"))
      (node (ref "IC7") (pin "4") (pinfunction "QE_4") (pintype "tri_state"))
    )
    (net (code "163") (name "PC5") (class "Default")
      (node (ref "E40") (pin "34") (pinfunction "34_34") (pintype "passive"))
      (node (ref "IC8") (pin "1") (pinfunction "QB_1") (pintype "tri_state"))
    )
    (net (code "164") (name "PC6") (class "Default")
      (node (ref "F40") (pin "1") (pinfunction "1_1") (pintype "passive"))
      (node (ref "IC9") (pin "15") (pinfunction "QA_15") (pintype "tri_state"))
    )
    (net (code "165") (name "PC7") (class "Default")
      (node (ref "F40") (pin "10") (pinfunction "10_10") (pintype "passive"))
      (node (ref "IC9") (pin "5") (pinfunction "QF_5") (pintype "tri_state"))
    )
    (net (code "166") (name "PC8") (class "Default")
      (node (ref "F40") (pin "11") (pinfunction "11_11") (pintype "passive"))
      (node (ref "IC10") (pin "2") (pinfunction "QC_2") (pintype "tri_state"))
    )
    (net (code "167") (name "PC9") (class "Default")
      (node (ref "F40") (pin "24") (pinfunction "24_24") (pintype "passive"))
      (node (ref "IC10") (pin "7") (pinfunction "QH_7") (pintype "tri_state"))
    )
    (net (code "168") (name "PC10") (class "Default")
      (node (ref "F40") (pin "25") (pinfunction "25_25") (pintype "passive"))
      (node (ref "IC11") (pin "4") (pinfunction "QE_4") (pintype "tri_state"))
    )
    (net (code "169") (name "PC11") (class "Default")
      (node (ref "F40") (pin "34") (pinfunction "34_34") (pintype "passive"))
      (node (ref "IC12") (pin "1") (pinfunction "QB_1") (pintype "tri_state"))
    )
    (net (code "170") (name "RCK") (class "Default")
      (node (ref "IC1") (pin "12") (pinfunction "RCK_12") (pintype "input"))
      (node (ref "IC10") (pin "12") (pinfunction "RCK_12") (pintype "input"))
      (node (ref "IC11") (pin "12") (pinfunction "RCK_12") (pintype "input"))
      (node (ref "IC12") (pin "12") (pinfunction "RCK_12") (pintype "input"))
      (node (ref "IC13") (pin "12") (pinfunction "RCK_12") (pintype "input"))
      (node (ref "IC16") (pin "12") (pinfunction "RCK_12") (pintype "input"))
      (node (ref "IC19") (pin "6") (pinfunction "O_6") (pintype "output"))
      (node (ref "IC4") (pin "12") (pinfunction "RCK_12") (pintype "input"))
      (node (ref "IC5") (pin "12") (pinfunction "RCK_12") (pintype "input"))
      (node (ref "IC6") (pin "12") (pinfunction "RCK_12") (pintype "input"))
      (node (ref "IC7") (pin "12") (pinfunction "RCK_12") (pintype "input"))
      (node (ref "IC8") (pin "12") (pinfunction "RCK_12") (pintype "input"))
      (node (ref "IC9") (pin "12") (pinfunction "RCK_12") (pintype "input"))
      (node (ref "SV1") (pin "7") (pinfunction "7_7") (pintype "passive"))
      (node (ref "SV2") (pin "7") (pinfunction "7_7") (pintype "passive"))
    )
    (net (code "171") (name "RESET-TRIG#") (class "Default")
      (node (ref "R23") (pin "1") (pinfunction "1_1") (pintype "passive"))
      (node (ref "XESS") (pin "21") (pinfunction "D15_21") (pintype "bidirectional"))
    )
    (net (code "172") (name "RS232-RD") (class "Default")
      (node (ref "D1") (pin "C") (pinfunction "C_C") (pintype "passive"))
      (node (ref "R2") (pin "1") (pinfunction "1_1") (pintype "passive"))
      (node (ref "XESS") (pin "31") (pinfunction "G5_31") (pintype "bidirectional"))
    )
    (net (code "173") (name "RS232-RTS") (class "Default")
      (node (ref "R3") (pin "1") (pinfunction "1_1") (pintype "passive"))
      (node (ref "XESS") (pin "26") (pinfunction "F4_26") (pintype "bidirectional"))
    )
    (net (code "174") (name "RS232-TD") (class "Default")
      (node (ref "R1") (pin "1") (pinfunction "1_1") (pintype "passive"))
      (node (ref "XESS") (pin "41") (pinfunction "J2_41") (pintype "bidirectional"))
    )
    (net (code "175") (name "RTS") (class "Default")
      (node (ref "IC3") (pin "7") (pinfunction "T2OUT_7") (pintype "output"))
      (node (ref "RS-232") (pin "5") (pinfunction "5_5") (pintype "passive"))
      (node (ref "X1") (pin "8") (pinfunction "F_8") (pintype "passive"))
    )
    (net (code "176") (name "RUN") (class "Default")
      (node (ref "D40") (pin "33") (pinfunction "33_33") (pintype "passive"))
      (node (ref "IC16") (pin "2") (pinfunction "QC_2") (pintype "tri_state"))
    )
    (net (code "177") (name "RXD") (class "Default")
      (node (ref "IC3") (pin "8") (pinfunction "R2IN_8") (pintype "input"))
      (node (ref "RS-232") (pin "4") (pinfunction "4_4") (pintype "passive"))
      (node (ref "X1") (pin "3") (pinfunction "F_3") (pintype "passive"))
    )
    (net (code "178") (name "SC0") (class "Default")
      (node (ref "C40") (pin "9") (pinfunction "9_9") (pintype "passive"))
      (node (ref "IC1") (pin "1") (pinfunction "QB_1") (pintype "tri_state"))
    )
    (net (code "179") (name "SC1") (class "Default")
      (node (ref "C40") (pin "2") (pinfunction "2_2") (pintype "passive"))
      (node (ref "IC1") (pin "3") (pinfunction "QD_3") (pintype "tri_state"))
    )
    (net (code "180") (name "SC2") (class "Default")
      (node (ref "C40") (pin "23") (pinfunction "23_23") (pintype "passive"))
      (node (ref "IC1") (pin "5") (pinfunction "QF_5") (pintype "tri_state"))
    )
    (net (code "181") (name "SC3") (class "Default")
      (node (ref "C40") (pin "12") (pinfunction "12_12") (pintype "passive"))
      (node (ref "IC1") (pin "7") (pinfunction "QH_7") (pintype "tri_state"))
    )
    (net (code "182") (name "SC4") (class "Default")
      (node (ref "C40") (pin "33") (pinfunction "33_33") (pintype "passive"))
      (node (ref "IC4") (pin "1") (pinfunction "QB_1") (pintype "tri_state"))
    )
    (net (code "183") (name "SCLK") (class "Default")
      (node (ref "IC14") (pin "2") (pinfunction "CLK_2") (pintype "input"))
      (node (ref "IC15") (pin "2") (pinfunction "CLK_2") (pintype "input"))
      (node (ref "IC17") (pin "5") (pinfunction "Y3_5") (pintype "tri_state"))
      (node (ref "IC18") (pin "2") (pinfunction "CLK_2") (pintype "input"))
      (node (ref "IC2") (pin "2") (pinfunction "CLK_2") (pintype "input"))
      (node (ref "SV1") (pin "10") (pinfunction "10_10") (pintype "passive"))
      (node (ref "SV2") (pin "10") (pinfunction "10_10") (pintype "passive"))
    )
    (net (code "184") (name "SD-CD#") (class "Default")
      (node (ref "J4") (pin "10") (pinfunction "CD#_10") (pintype "output"))
      (node (ref "R4") (pin "1") (pinfunction "1_1") (pintype "passive"))
      (node (ref "XESS") (pin "4") (pinfunction "H14_4") (pintype "bidirectional"))
    )
    (net (code "185") (name "SD-CLK") (class "Default")
      (node (ref "J4") (pin "5") (pinfunction "CLK/SCLK_5") (pintype "bidirectional"))
      (node (ref "XESS") (pin "1") (pinfunction "H16_1") (pintype "bidirectional"))
    )
    (net (code "186") (name "SD-CMD") (class "Default")
      (node (ref "J4") (pin "2") (pinfunction "CMD/DI_2") (pintype "bidirectional"))
      (node (ref "XESS") (pin "45") (pinfunction "K5_45") (pintype "bidirectional"))
    )
    (net (code "187") (name "SD-DAT0") (class "Default")
      (node (ref "J4") (pin "7") (pinfunction "DAT0_7") (pintype "bidirectional"))
      (node (ref "XESS") (pin "66") (pinfunction "M10_66") (pintype "bidirectional"))
    )
    (net (code "188") (name "SD-DAT1") (class "Default")
      (node (ref "J4") (pin "8") (pinfunction "DAT1_8") (pintype "bidirectional"))
      (node (ref "XESS") (pin "67") (pinfunction "P11_67") (pintype "bidirectional"))
    )
    (net (code "189") (name "SD-DAT2") (class "Default")
      (node (ref "J4") (pin "9") (pinfunction "DAT2_9") (pintype "bidirectional"))
      (node (ref "XESS") (pin "68") (pinfunction "T12_68") (pintype "bidirectional"))
    )
    (net (code "190") (name "SD-DAT3") (class "Default")
      (node (ref "J4") (pin "1") (pinfunction "CD/DAT3_1") (pintype "bidirectional"))
      (node (ref "XESS") (pin "69") (pinfunction "R12_69") (pintype "bidirectional"))
    )
    (net (code "191") (name "SD-WP") (class "Default")
      (node (ref "J4") (pin "12") (pinfunction "WP_12") (pintype "output"))
      (node (ref "R5") (pin "1") (pinfunction "1_1") (pintype "passive"))
      (node (ref "XESS") (pin "5") (pinfunction "H13_5") (pintype "bidirectional"))
    )
    (net (code "192") (name "SDF0") (class "Default")
      (node (ref "A40") (pin "6") (pinfunction "6_6") (pintype "passive"))
      (node (ref "IC14") (pin "11") (pinfunction "A_11") (pintype "input"))
      (node (ref "R24") (pin "1") (pinfunction "1_1") (pintype "passive"))
    )
    (net (code "193") (name "SDF1") (class "Default")
      (node (ref "A40") (pin "8") (pinfunction "8_8") (pintype "passive"))
      (node (ref "IC14") (pin "12") (pinfunction "B_12") (pintype "input"))
      (node (ref "R25") (pin "1") (pinfunction "1_1") (pintype "passive"))
    )
    (net (code "194") (name "SDF2") (class "Default")
      (node (ref "A40") (pin "10") (pinfunction "10_10") (pintype "passive"))
      (node (ref "IC14") (pin "13") (pinfunction "C_13") (pintype "input"))
      (node (ref "R26") (pin "1") (pinfunction "1_1") (pintype "passive"))
    )
    (net (code "195") (name "SI") (class "Default")
      (node (ref "B40") (pin "32") (pinfunction "32_32") (pintype "passive"))
      (node (ref "IC18") (pin "12") (pinfunction "B_12") (pintype "input"))
      (node (ref "R49") (pin "1") (pinfunction "1_1") (pintype "passive"))
    )
    (net (code "196") (name "SIF0") (class "Default")
      (node (ref "A40") (pin "12") (pinfunction "12_12") (pintype "passive"))
      (node (ref "IC14") (pin "14") (pinfunction "D_14") (pintype "input"))
      (node (ref "R27") (pin "1") (pinfunction "1_1") (pintype "passive"))
    )
    (net (code "197") (name "SIF1") (class "Default")
      (node (ref "A40") (pin "14") (pinfunction "14_14") (pintype "passive"))
      (node (ref "IC14") (pin "3") (pinfunction "E_3") (pintype "input"))
      (node (ref "R28") (pin "1") (pinfunction "1_1") (pintype "passive"))
    )
    (net (code "198") (name "SIF2") (class "Default")
      (node (ref "A40") (pin "16") (pinfunction "16_16") (pintype "passive"))
      (node (ref "IC14") (pin "4") (pinfunction "F_4") (pintype "input"))
      (node (ref "R29") (pin "1") (pinfunction "1_1") (pintype "passive"))
    )
    (net (code "199") (name "SLOT1-CS#") (class "Default")
      (node (ref "SLOT1") (pin "37") (pinfunction "37_37") (pintype "passive"))
      (node (ref "XESS") (pin "18") (pinfunction "E15_18") (pintype "bidirectional"))
    )
    (net (code "200") (name "SLOT1-IRQ") (class "Default")
      (node (ref "R21") (pin "1") (pinfunction "1_1") (pintype "passive"))
      (node (ref "XESS") (pin "84") (pinfunction "J16_84") (pintype "bidirectional"))
    )
    (net (code "201") (name "SLOT2-CS#") (class "Default")
      (node (ref "SLOT2") (pin "37") (pinfunction "37_37") (pintype "passive"))
      (node (ref "XESS") (pin "19") (pinfunction "D16_19") (pintype "bidirectional"))
    )
    (net (code "202") (name "SLOT2-IRQ") (class "Default")
      (node (ref "R22") (pin "1") (pinfunction "1_1") (pintype "passive"))
      (node (ref "XESS") (pin "83") (pinfunction "J14_83") (pintype "bidirectional"))
    )
    (net (code "203") (name "SR0") (class "Default")
      (node (ref "A40") (pin "18") (pinfunction "18_18") (pintype "passive"))
      (node (ref "IC14") (pin "5") (pinfunction "G_5") (pintype "input"))
      (node (ref "R30") (pin "1") (pinfunction "1_1") (pintype "passive"))
    )
    (net (code "204") (name "SR1") (class "Default")
      (node (ref "A40") (pin "20") (pinfunction "20_20") (pintype "passive"))
      (node (ref "IC14") (pin "6") (pinfunction "H_6") (pintype "input"))
      (node (ref "R31") (pin "1") (pinfunction "1_1") (pintype "passive"))
    )
    (net (code "205") (name "SR2") (class "Default")
      (node (ref "A40") (pin "26") (pinfunction "26_26") (pintype "passive"))
      (node (ref "IC15") (pin "11") (pinfunction "A_11") (pintype "input"))
      (node (ref "R32") (pin "1") (pinfunction "1_1") (pintype "passive"))
    )
    (net (code "206") (name "SR3") (class "Default")
      (node (ref "A40") (pin "28") (pinfunction "28_28") (pintype "passive"))
      (node (ref "IC15") (pin "12") (pinfunction "B_12") (pintype "input"))
      (node (ref "R33") (pin "1") (pinfunction "1_1") (pintype "passive"))
    )
    (net (code "207") (name "SR4") (class "Default")
      (node (ref "A40") (pin "30") (pinfunction "30_30") (pintype "passive"))
      (node (ref "IC15") (pin "13") (pinfunction "C_13") (pintype "input"))
      (node (ref "R34") (pin "1") (pinfunction "1_1") (pintype "passive"))
    )
    (net (code "208") (name "SR5") (class "Default")
      (node (ref "A40") (pin "34") (pinfunction "34_34") (pintype "passive"))
      (node (ref "IC15") (pin "14") (pinfunction "D_14") (pintype "input"))
      (node (ref "R35") (pin "1") (pinfunction "1_1") (pintype "passive"))
    )
    (net (code "209") (name "SR6") (class "Default")
      (node (ref "A40") (pin "32") (pinfunction "32_32") (pintype "passive"))
      (node (ref "IC15") (pin "3") (pinfunction "E_3") (pintype "input"))
      (node (ref "R36") (pin "1") (pinfunction "1_1") (pintype "passive"))
    )
    (net (code "210") (name "SR7") (class "Default")
      (node (ref "B40") (pin "6") (pinfunction "6_6") (pintype "passive"))
      (node (ref "IC15") (pin "4") (pinfunction "F_4") (pintype "input"))
      (node (ref "R37") (pin "1") (pinfunction "1_1") (pintype "passive"))
    )
    (net (code "211") (name "SR8") (class "Default")
      (node (ref "B40") (pin "8") (pinfunction "8_8") (pintype "passive"))
      (node (ref "IC15") (pin "5") (pinfunction "G_5") (pintype "input"))
      (node (ref "R38") (pin "1") (pinfunction "1_1") (pintype "passive"))
    )
    (net (code "212") (name "SR9") (class "Default")
      (node (ref "B40") (pin "10") (pinfunction "10_10") (pintype "passive"))
      (node (ref "IC15") (pin "6") (pinfunction "H_6") (pintype "input"))
      (node (ref "R39") (pin "1") (pinfunction "1_1") (pintype "passive"))
    )
    (net (code "213") (name "SR10") (class "Default")
      (node (ref "B40") (pin "12") (pinfunction "12_12") (pintype "passive"))
      (node (ref "IC2") (pin "11") (pinfunction "A_11") (pintype "input"))
      (node (ref "R40") (pin "1") (pinfunction "1_1") (pintype "passive"))
    )
    (net (code "214") (name "SR11") (class "Default")
      (node (ref "B40") (pin "14") (pinfunction "14_14") (pintype "passive"))
      (node (ref "IC2") (pin "12") (pinfunction "B_12") (pintype "input"))
      (node (ref "R41") (pin "1") (pinfunction "1_1") (pintype "passive"))
    )
    (net (code "215") (name "SS") (class "Default")
      (node (ref "B40") (pin "34") (pinfunction "34_34") (pintype "passive"))
      (node (ref "IC18") (pin "11") (pinfunction "A_11") (pintype "input"))
      (node (ref "R48") (pin "1") (pinfunction "1_1") (pintype "passive"))
    )
    (net (code "216") (name "SSER") (class "Default")
      (node (ref "IC17") (pin "13") (pinfunction "A2_13") (pintype "input"))
      (node (ref "IC18") (pin "9") (pinfunction "QH_9") (pintype "output"))
      (node (ref "SV1") (pin "8") (pinfunction "8_8") (pintype "passive"))
      (node (ref "SV2") (pin "8") (pinfunction "8_8") (pintype "passive"))
    )
    (net (code "217") (name "START") (class "Default")
      (node (ref "B40") (pin "16") (pinfunction "16_16") (pintype "passive"))
      (node (ref "IC2") (pin "13") (pinfunction "C_13") (pintype "input"))
      (node (ref "R42") (pin "1") (pinfunction "1_1") (pintype "passive"))
    )
    (net (code "218") (name "STOP") (class "Default")
      (node (ref "B40") (pin "30") (pinfunction "30_30") (pintype "passive"))
      (node (ref "IC2") (pin "6") (pinfunction "H_6") (pintype "input"))
      (node (ref "R47") (pin "1") (pinfunction "1_1") (pintype "passive"))
    )
    (net (code "219") (name "TAD") (class "Default")
      (node (ref "D40") (pin "4") (pinfunction "4_4") (pintype "passive"))
      (node (ref "IC13") (pin "2") (pinfunction "QC_2") (pintype "tri_state"))
    )
    (net (code "220") (name "TXD") (class "Default")
      (node (ref "IC3") (pin "13") (pinfunction "R1IN_13") (pintype "input"))
      (node (ref "IC3") (pin "14") (pinfunction "T1OUT_14") (pintype "output"))
      (node (ref "RS-232") (pin "2") (pinfunction "2_2") (pintype "passive"))
      (node (ref "X1") (pin "2") (pinfunction "F_2") (pintype "passive"))
    )
    (net (code "221") (name "VCC") (class "Default")
      (node (ref "+V1") (pin "1") (pinfunction "1_1") (pintype "passive"))
      (node (ref "+V2") (pin "1") (pinfunction "1_1") (pintype "passive"))
      (node (ref "+V3") (pin "1") (pinfunction "1_1") (pintype "passive"))
      (node (ref "+V4") (pin "1") (pinfunction "1_1") (pintype "passive"))
      (node (ref "5V") (pin "1") (pinfunction "1_1") (pintype "passive"))
      (node (ref "C1") (pin "1") (pinfunction "1_1") (pintype "passive"))
      (node (ref "C10") (pin "1") (pinfunction "1_1") (pintype "passive"))
      (node (ref "C11") (pin "1") (pinfunction "1_1") (pintype "passive"))
      (node (ref "C12") (pin "1") (pinfunction "1_1") (pintype "passive"))
      (node (ref "C13") (pin "1") (pinfunction "1_1") (pintype "passive"))
      (node (ref "C14") (pin "1") (pinfunction "1_1") (pintype "passive"))
      (node (ref "C15") (pin "1") (pinfunction "1_1") (pintype "passive"))
      (node (ref "C16") (pin "1") (pinfunction "1_1") (pintype "passive"))
      (node (ref "C17") (pin "1") (pinfunction "1_1") (pintype "passive"))
      (node (ref "C18") (pin "1") (pinfunction "1_1") (pintype "passive"))
      (node (ref "C19") (pin "1") (pinfunction "1_1") (pintype "passive"))
      (node (ref "C20") (pin "1") (pinfunction "1_1") (pintype "passive"))
      (node (ref "C21") (pin "1") (pinfunction "1_1") (pintype "passive"))
      (node (ref "C22") (pin "1") (pinfunction "1_1") (pintype "passive"))
      (node (ref "C23") (pin "1") (pinfunction "1_1") (pintype "passive"))
      (node (ref "C24") (pin "1") (pinfunction "1_1") (pintype "passive"))
      (node (ref "C6") (pin "1") (pinfunction "1_1") (pintype "passive"))
      (node (ref "C7") (pin "1") (pinfunction "1_1") (pintype "passive"))
      (node (ref "C8") (pin "1") (pinfunction "1_1") (pintype "passive"))
      (node (ref "C9") (pin "1") (pinfunction "1_1") (pintype "passive"))
      (node (ref "J1") (pin "4") (pinfunction "4_4") (pintype "passive"))
      (node (ref "R10") (pin "1") (pinfunction "1_1") (pintype "passive"))
      (node (ref "R24") (pin "2") (pinfunction "2_2") (pintype "passive"))
      (node (ref "R25") (pin "2") (pinfunction "2_2") (pintype "passive"))
      (node (ref "R26") (pin "2") (pinfunction "2_2") (pintype "passive"))
      (node (ref "R27") (pin "2") (pinfunction "2_2") (pintype "passive"))
      (node (ref "R28") (pin "2") (pinfunction "2_2") (pintype "passive"))
      (node (ref "R29") (pin "2") (pinfunction "2_2") (pintype "passive"))
      (node (ref "R30") (pin "2") (pinfunction "2_2") (pintype "passive"))
      (node (ref "R31") (pin "2") (pinfunction "2_2") (pintype "passive"))
      (node (ref "R32") (pin "2") (pinfunction "2_2") (pintype "passive"))
      (node (ref "R33") (pin "2") (pinfunction "2_2") (pintype "passive"))
      (node (ref "R34") (pin "2") (pinfunction "2_2") (pintype "passive"))
      (node (ref "R35") (pin "2") (pinfunction "2_2") (pintype "passive"))
      (node (ref "R36") (pin "2") (pinfunction "2_2") (pintype "passive"))
      (node (ref "R37") (pin "2") (pinfunction "2_2") (pintype "passive"))
      (node (ref "R38") (pin "2") (pinfunction "2_2") (pintype "passive"))
      (node (ref "R39") (pin "2") (pinfunction "2_2") (pintype "passive"))
      (node (ref "R40") (pin "2") (pinfunction "2_2") (pintype "passive"))
      (node (ref "R41") (pin "2") (pinfunction "2_2") (pintype "passive"))
      (node (ref "R42") (pin "2") (pinfunction "2_2") (pintype "passive"))
      (node (ref "R43") (pin "2") (pinfunction "2_2") (pintype "passive"))
      (node (ref "R44") (pin "2") (pinfunction "2_2") (pintype "passive"))
      (node (ref "R45") (pin "2") (pinfunction "2_2") (pintype "passive"))
      (node (ref "R46") (pin "2") (pinfunction "2_2") (pintype "passive"))
      (node (ref "R47") (pin "2") (pinfunction "2_2") (pintype "passive"))
      (node (ref "R48") (pin "2") (pinfunction "2_2") (pintype "passive"))
      (node (ref "R49") (pin "2") (pinfunction "2_2") (pintype "passive"))
      (node (ref "R50") (pin "1") (pinfunction "1_1") (pintype "passive"))
      (node (ref "R6") (pin "1") (pinfunction "1_1") (pintype "passive"))
      (node (ref "R7") (pin "1") (pinfunction "1_1") (pintype "passive"))
      (node (ref "R8") (pin "1") (pinfunction "1_1") (pintype "passive"))
      (node (ref "R9") (pin "1") (pinfunction "1_1") (pintype "passive"))
    )
    (net (code "222") (name "VDD") (class "Default")
      (node (ref "3.3V") (pin "2") (pinfunction "2_2") (pintype "passive"))
      (node (ref "J4") (pin "4") (pinfunction "VDD_4") (pintype "power_in"))
    )
    (net (code "223") (name "VSS") (class "Default")
      (node (ref "J3") (pin "1") (pinfunction "1_1") (pintype "passive"))
      (node (ref "J4") (pin "3") (pinfunction "VSS_3") (pintype "power_in"))
      (node (ref "J4") (pin "6") (pinfunction "VSS_6") (pintype "power_in"))
    )
    (net (code "224") (name "WC") (class "Default")
      (node (ref "D40") (pin "30") (pinfunction "30_30") (pintype "passive"))
      (node (ref "IC16") (pin "5") (pinfunction "QF_5") (pintype "tri_state"))
    )
    (net (code "225") (name "unconnected-(A40-Pad1)") (class "Default")
      (node (ref "A40") (pin "1") (pinfunction "1_1") (pintype "passive"))
    )
    (net (code "226") (name "unconnected-(A40-Pad2)") (class "Default")
      (node (ref "A40") (pin "2") (pinfunction "2_2") (pintype "passive"))
    )
    (net (code "227") (name "unconnected-(A40-Pad3)") (class "Default")
      (node (ref "A40") (pin "3") (pinfunction "3_3") (pintype "passive"))
    )
    (net (code "228") (name "unconnected-(A40-Pad5)") (class "Default")
      (node (ref "A40") (pin "5") (pinfunction "5_5") (pintype "passive"))
    )
    (net (code "229") (name "unconnected-(A40-Pad7)") (class "Default")
      (node (ref "A40") (pin "7") (pinfunction "7_7") (pintype "passive"))
    )
    (net (code "230") (name "unconnected-(A40-Pad9)") (class "Default")
      (node (ref "A40") (pin "9") (pinfunction "9_9") (pintype "passive"))
    )
    (net (code "231") (name "unconnected-(A40-Pad11)") (class "Default")
      (node (ref "A40") (pin "11") (pinfunction "11_11") (pintype "passive"))
    )
    (net (code "232") (name "unconnected-(A40-Pad13)") (class "Default")
      (node (ref "A40") (pin "13") (pinfunction "13_13") (pintype "passive"))
    )
    (net (code "233") (name "unconnected-(A40-Pad15)") (class "Default")
      (node (ref "A40") (pin "15") (pinfunction "15_15") (pintype "passive"))
    )
    (net (code "234") (name "unconnected-(A40-Pad17)") (class "Default")
      (node (ref "A40") (pin "17") (pinfunction "17_17") (pintype "passive"))
    )
    (net (code "235") (name "unconnected-(A40-Pad19)") (class "Default")
      (node (ref "A40") (pin "19") (pinfunction "19_19") (pintype "passive"))
    )
    (net (code "236") (name "unconnected-(A40-Pad21)") (class "Default")
      (node (ref "A40") (pin "21") (pinfunction "21_21") (pintype "passive"))
    )
    (net (code "237") (name "unconnected-(A40-Pad22)") (class "Default")
      (node (ref "A40") (pin "22") (pinfunction "22_22") (pintype "passive"))
    )
    (net (code "238") (name "unconnected-(A40-Pad23)") (class "Default")
      (node (ref "A40") (pin "23") (pinfunction "23_23") (pintype "passive"))
    )
    (net (code "239") (name "unconnected-(A40-Pad24)") (class "Default")
      (node (ref "A40") (pin "24") (pinfunction "24_24") (pintype "passive"))
    )
    (net (code "240") (name "unconnected-(A40-Pad25)") (class "Default")
      (node (ref "A40") (pin "25") (pinfunction "25_25") (pintype "passive"))
    )
    (net (code "241") (name "unconnected-(A40-Pad27)") (class "Default")
      (node (ref "A40") (pin "27") (pinfunction "27_27") (pintype "passive"))
    )
    (net (code "242") (name "unconnected-(A40-Pad29)") (class "Default")
      (node (ref "A40") (pin "29") (pinfunction "29_29") (pintype "passive"))
    )
    (net (code "243") (name "unconnected-(A40-Pad31)") (class "Default")
      (node (ref "A40") (pin "31") (pinfunction "31_31") (pintype "passive"))
    )
    (net (code "244") (name "unconnected-(A40-Pad33)") (class "Default")
      (node (ref "A40") (pin "33") (pinfunction "33_33") (pintype "passive"))
    )
    (net (code "245") (name "unconnected-(B40-Pad1)") (class "Default")
      (node (ref "B40") (pin "1") (pinfunction "1_1") (pintype "passive"))
    )
    (net (code "246") (name "unconnected-(B40-Pad2)") (class "Default")
      (node (ref "B40") (pin "2") (pinfunction "2_2") (pintype "passive"))
    )
    (net (code "247") (name "unconnected-(B40-Pad3)") (class "Default")
      (node (ref "B40") (pin "3") (pinfunction "3_3") (pintype "passive"))
    )
    (net (code "248") (name "unconnected-(B40-Pad5)") (class "Default")
      (node (ref "B40") (pin "5") (pinfunction "5_5") (pintype "passive"))
    )
    (net (code "249") (name "unconnected-(B40-Pad7)") (class "Default")
      (node (ref "B40") (pin "7") (pinfunction "7_7") (pintype "passive"))
    )
    (net (code "250") (name "unconnected-(B40-Pad9)") (class "Default")
      (node (ref "B40") (pin "9") (pinfunction "9_9") (pintype "passive"))
    )
    (net (code "251") (name "unconnected-(B40-Pad11)") (class "Default")
      (node (ref "B40") (pin "11") (pinfunction "11_11") (pintype "passive"))
    )
    (net (code "252") (name "unconnected-(B40-Pad13)") (class "Default")
      (node (ref "B40") (pin "13") (pinfunction "13_13") (pintype "passive"))
    )
    (net (code "253") (name "unconnected-(B40-Pad15)") (class "Default")
      (node (ref "B40") (pin "15") (pinfunction "15_15") (pintype "passive"))
    )
    (net (code "254") (name "unconnected-(B40-Pad17)") (class "Default")
      (node (ref "B40") (pin "17") (pinfunction "17_17") (pintype "passive"))
    )
    (net (code "255") (name "unconnected-(B40-Pad19)") (class "Default")
      (node (ref "B40") (pin "19") (pinfunction "19_19") (pintype "passive"))
    )
    (net (code "256") (name "unconnected-(B40-Pad21)") (class "Default")
      (node (ref "B40") (pin "21") (pinfunction "21_21") (pintype "passive"))
    )
    (net (code "257") (name "unconnected-(B40-Pad22)") (class "Default")
      (node (ref "B40") (pin "22") (pinfunction "22_22") (pintype "passive"))
    )
    (net (code "258") (name "unconnected-(B40-Pad23)") (class "Default")
      (node (ref "B40") (pin "23") (pinfunction "23_23") (pintype "passive"))
    )
    (net (code "259") (name "unconnected-(B40-Pad24)") (class "Default")
      (node (ref "B40") (pin "24") (pinfunction "24_24") (pintype "passive"))
    )
    (net (code "260") (name "unconnected-(B40-Pad25)") (class "Default")
      (node (ref "B40") (pin "25") (pinfunction "25_25") (pintype "passive"))
    )
    (net (code "261") (name "unconnected-(B40-Pad27)") (class "Default")
      (node (ref "B40") (pin "27") (pinfunction "27_27") (pintype "passive"))
    )
    (net (code "262") (name "unconnected-(B40-Pad29)") (class "Default")
      (node (ref "B40") (pin "29") (pinfunction "29_29") (pintype "passive"))
    )
    (net (code "263") (name "unconnected-(B40-Pad31)") (class "Default")
      (node (ref "B40") (pin "31") (pinfunction "31_31") (pintype "passive"))
    )
    (net (code "264") (name "unconnected-(B40-Pad33)") (class "Default")
      (node (ref "B40") (pin "33") (pinfunction "33_33") (pintype "passive"))
    )
    (net (code "265") (name "unconnected-(C40-Pad3)") (class "Default")
      (node (ref "C40") (pin "3") (pinfunction "3_3") (pintype "passive"))
    )
    (net (code "266") (name "unconnected-(C40-Pad4)") (class "Default")
      (node (ref "C40") (pin "4") (pinfunction "4_4") (pintype "passive"))
    )
    (net (code "267") (name "unconnected-(C40-Pad5)") (class "Default")
      (node (ref "C40") (pin "5") (pinfunction "5_5") (pintype "passive"))
    )
    (net (code "268") (name "unconnected-(C40-Pad6)") (class "Default")
      (node (ref "C40") (pin "6") (pinfunction "6_6") (pintype "passive"))
    )
    (net (code "269") (name "unconnected-(C40-Pad7)") (class "Default")
      (node (ref "C40") (pin "7") (pinfunction "7_7") (pintype "passive"))
    )
    (net (code "270") (name "unconnected-(C40-Pad8)") (class "Default")
      (node (ref "C40") (pin "8") (pinfunction "8_8") (pintype "passive"))
    )
    (net (code "271") (name "unconnected-(C40-Pad13)") (class "Default")
      (node (ref "C40") (pin "13") (pinfunction "13_13") (pintype "passive"))
    )
    (net (code "272") (name "unconnected-(C40-Pad14)") (class "Default")
      (node (ref "C40") (pin "14") (pinfunction "14_14") (pintype "passive"))
    )
    (net (code "273") (name "unconnected-(C40-Pad15)") (class "Default")
      (node (ref "C40") (pin "15") (pinfunction "15_15") (pintype "passive"))
    )
    (net (code "274") (name "unconnected-(C40-Pad16)") (class "Default")
      (node (ref "C40") (pin "16") (pinfunction "16_16") (pintype "passive"))
    )
    (net (code "275") (name "unconnected-(C40-Pad21)") (class "Default")
      (node (ref "C40") (pin "21") (pinfunction "21_21") (pintype "passive"))
    )
    (net (code "276") (name "unconnected-(C40-Pad22)") (class "Default")
      (node (ref "C40") (pin "22") (pinfunction "22_22") (pintype "passive"))
    )
    (net (code "277") (name "unconnected-(C40-Pad26)") (class "Default")
      (node (ref "C40") (pin "26") (pinfunction "26_26") (pintype "passive"))
    )
    (net (code "278") (name "unconnected-(C40-Pad27)") (class "Default")
      (node (ref "C40") (pin "27") (pinfunction "27_27") (pintype "passive"))
    )
    (net (code "279") (name "unconnected-(C40-Pad29)") (class "Default")
      (node (ref "C40") (pin "29") (pinfunction "29_29") (pintype "passive"))
    )
    (net (code "280") (name "unconnected-(C40-Pad30)") (class "Default")
      (node (ref "C40") (pin "30") (pinfunction "30_30") (pintype "passive"))
    )
    (net (code "281") (name "unconnected-(C40-Pad31)") (class "Default")
      (node (ref "C40") (pin "31") (pinfunction "31_31") (pintype "passive"))
    )
    (net (code "282") (name "unconnected-(C40-Pad32)") (class "Default")
      (node (ref "C40") (pin "32") (pinfunction "32_32") (pintype "passive"))
    )
    (net (code "283") (name "unconnected-(CONFIGSW-Pad7)") (class "Default")
      (node (ref "CONFIGSW") (pin "7") (pinfunction "7_7") (pintype "passive"))
    )
    (net (code "284") (name "unconnected-(CONFIGSW-Pad8)") (class "Default")
      (node (ref "CONFIGSW") (pin "8") (pinfunction "8_8") (pintype "passive"))
    )
    (net (code "285") (name "unconnected-(CONFIGSW-Pad9)") (class "Default")
      (node (ref "CONFIGSW") (pin "9") (pinfunction "9_9") (pintype "passive"))
    )
    (net (code "286") (name "unconnected-(D40-Pad1)") (class "Default")
      (node (ref "D40") (pin "1") (pinfunction "1_1") (pintype "passive"))
    )
    (net (code "287") (name "unconnected-(D40-Pad3)") (class "Default")
      (node (ref "D40") (pin "3") (pinfunction "3_3") (pintype "passive"))
    )
    (net (code "288") (name "unconnected-(D40-Pad5)") (class "Default")
      (node (ref "D40") (pin "5") (pinfunction "5_5") (pintype "passive"))
    )
    (net (code "289") (name "unconnected-(D40-Pad7)") (class "Default")
      (node (ref "D40") (pin "7") (pinfunction "7_7") (pintype "passive"))
    )
    (net (code "290") (name "unconnected-(D40-Pad9)") (class "Default")
      (node (ref "D40") (pin "9") (pinfunction "9_9") (pintype "passive"))
    )
    (net (code "291") (name "unconnected-(D40-Pad11)") (class "Default")
      (node (ref "D40") (pin "11") (pinfunction "11_11") (pintype "passive"))
    )
    (net (code "292") (name "unconnected-(D40-Pad13)") (class "Default")
      (node (ref "D40") (pin "13") (pinfunction "13_13") (pintype "passive"))
    )
    (net (code "293") (name "unconnected-(D40-Pad14)") (class "Default")
      (node (ref "D40") (pin "14") (pinfunction "14_14") (pintype "passive"))
    )
    (net (code "294") (name "unconnected-(D40-Pad15)") (class "Default")
      (node (ref "D40") (pin "15") (pinfunction "15_15") (pintype "passive"))
    )
    (net (code "295") (name "unconnected-(D40-Pad21)") (class "Default")
      (node (ref "D40") (pin "21") (pinfunction "21_21") (pintype "passive"))
    )
    (net (code "296") (name "unconnected-(D40-Pad25)") (class "Default")
      (node (ref "D40") (pin "25") (pinfunction "25_25") (pintype "passive"))
    )
    (net (code "297") (name "unconnected-(D40-Pad27)") (class "Default")
      (node (ref "D40") (pin "27") (pinfunction "27_27") (pintype "passive"))
    )
    (net (code "298") (name "unconnected-(D40-Pad29)") (class "Default")
      (node (ref "D40") (pin "29") (pinfunction "29_29") (pintype "passive"))
    )
    (net (code "299") (name "unconnected-(IC2A-~{QH}-Pad7)") (class "Default")
      (node (ref "IC2") (pin "7") (pinfunction "~{QH}_7") (pintype "output"))
    )
    (net (code "300") (name "unconnected-(IC3A-R1OUT-Pad12)") (class "Default")
      (node (ref "IC3") (pin "12") (pinfunction "R1OUT_12") (pintype "output"))
    )
    (net (code "301") (name "unconnected-(IC4A-QE-Pad4)") (class "Default")
      (node (ref "IC4") (pin "4") (pinfunction "QE_4") (pintype "tri_state"))
    )
    (net (code "302") (name "unconnected-(IC4A-QF-Pad5)") (class "Default")
      (node (ref "IC4") (pin "5") (pinfunction "QF_5") (pintype "tri_state"))
    )
    (net (code "303") (name "unconnected-(IC4A-QG-Pad6)") (class "Default")
      (node (ref "IC4") (pin "6") (pinfunction "QG_6") (pintype "tri_state"))
    )
    (net (code "304") (name "unconnected-(IC4A-QH-Pad7)") (class "Default")
      (node (ref "IC4") (pin "7") (pinfunction "QH_7") (pintype "tri_state"))
    )
    (net (code "305") (name "unconnected-(IC8A-QG-Pad6)") (class "Default")
      (node (ref "IC8") (pin "6") (pinfunction "QG_6") (pintype "tri_state"))
    )
    (net (code "306") (name "unconnected-(IC8A-QH-Pad7)") (class "Default")
      (node (ref "IC8") (pin "7") (pinfunction "QH_7") (pintype "tri_state"))
    )
    (net (code "307") (name "unconnected-(IC12A-QG-Pad6)") (class "Default")
      (node (ref "IC12") (pin "6") (pinfunction "QG_6") (pintype "tri_state"))
    )
    (net (code "308") (name "unconnected-(IC14A-~{QH}-Pad7)") (class "Default")
      (node (ref "IC14") (pin "7") (pinfunction "~{QH}_7") (pintype "output"))
    )
    (net (code "309") (name "unconnected-(IC15A-~{QH}-Pad7)") (class "Default")
      (node (ref "IC15") (pin "7") (pinfunction "~{QH}_7") (pintype "output"))
    )
    (net (code "310") (name "unconnected-(IC18A-~{QH}-Pad7)") (class "Default")
      (node (ref "IC18") (pin "7") (pinfunction "~{QH}_7") (pintype "output"))
    )
    (net (code "311") (name "unconnected-(IDE-Pad20)") (class "Default")
      (node (ref "IDE") (pin "20") (pinfunction "20_20") (pintype "passive"))
    )
    (net (code "312") (name "unconnected-(IDE-Pad32)") (class "Default")
      (node (ref "IDE") (pin "32") (pinfunction "32_32") (pintype "passive"))
    )
    (net (code "313") (name "unconnected-(IDE-Pad34)") (class "Default")
      (node (ref "IDE") (pin "34") (pinfunction "34_34") (pintype "passive"))
    )
    (net (code "314") (name "unconnected-(IDE-Pad39)") (class "Default")
      (node (ref "IDE") (pin "39") (pinfunction "39_39") (pintype "passive"))
    )
    (net (code "315") (name "unconnected-(RS-232-Pad1)") (class "Default")
      (node (ref "RS-232") (pin "1") (pinfunction "1_1") (pintype "passive"))
    )
    (net (code "316") (name "unconnected-(SLOT1-Pad34)") (class "Default")
      (node (ref "SLOT1") (pin "34") (pinfunction "34_34") (pintype "passive"))
    )
    (net (code "317") (name "unconnected-(SLOT2-Pad34)") (class "Default")
      (node (ref "SLOT2") (pin "34") (pinfunction "34_34") (pintype "passive"))
    )
    (net (code "318") (name "unconnected-(SV1-Pad2)") (class "Default")
      (node (ref "SV1") (pin "2") (pinfunction "2_2") (pintype "passive"))
    )
    (net (code "319") (name "unconnected-(SV1-Pad4)") (class "Default")
      (node (ref "SV1") (pin "4") (pinfunction "4_4") (pintype "passive"))
    )
    (net (code "320") (name "unconnected-(SV1-Pad6)") (class "Default")
      (node (ref "SV1") (pin "6") (pinfunction "6_6") (pintype "passive"))
    )
    (net (code "321") (name "unconnected-(SV2-Pad2)") (class "Default")
      (node (ref "SV2") (pin "2") (pinfunction "2_2") (pintype "passive"))
    )
    (net (code "322") (name "unconnected-(SV2-Pad4)") (class "Default")
      (node (ref "SV2") (pin "4") (pinfunction "4_4") (pintype "passive"))
    )
    (net (code "323") (name "unconnected-(SV2-Pad6)") (class "Default")
      (node (ref "SV2") (pin "6") (pinfunction "6_6") (pintype "passive"))
    )
    (net (code "324") (name "unconnected-(XESS-BSY-Pad17)") (class "Default")
      (node (ref "XESS") (pin "17") (pinfunction "BSY_17") (pintype "bidirectional"))
    )
    (net (code "325") (name "unconnected-(XESS-CLKB-Pad11)") (class "Default")
      (node (ref "XESS") (pin "11") (pinfunction "CLKB_11") (pintype "bidirectional"))
    )
    (net (code "326") (name "unconnected-(XESS-CLKC-Pad64)") (class "Default")
      (node (ref "XESS") (pin "64") (pinfunction "CLKC_64") (pintype "bidirectional"))
    )
    (net (code "327") (name "unconnected-(XESS-CS#-Pad15)") (class "Default")
      (node (ref "XESS") (pin "15") (pinfunction "CS#_15") (pintype "bidirectional"))
    )
    (net (code "328") (name "unconnected-(XESS-D1-Pad25)") (class "Default")
      (node (ref "XESS") (pin "25") (pinfunction "D1_25") (pintype "bidirectional"))
    )
    (net (code "329") (name "unconnected-(XESS-E14-Pad20)") (class "Default")
      (node (ref "XESS") (pin "20") (pinfunction "E14_20") (pintype "bidirectional"))
    )
    (net (code "330") (name "unconnected-(XESS-G13-Pad9)") (class "Default")
      (node (ref "XESS") (pin "9") (pinfunction "G13_9") (pintype "bidirectional"))
    )
    (net (code "331") (name "unconnected-(XESS-G16-Pad6)") (class "Default")
      (node (ref "XESS") (pin "6") (pinfunction "G16_6") (pintype "bidirectional"))
    )
    (net (code "332") (name "unconnected-(XESS-J3-Pad42)") (class "Default")
      (node (ref "XESS") (pin "42") (pinfunction "J3_42") (pintype "bidirectional"))
    )
    (net (code "333") (name "unconnected-(XESS-J13-Pad82)") (class "Default")
      (node (ref "XESS") (pin "82") (pinfunction "J13_82") (pintype "bidirectional"))
    )
    (net (code "334") (name "unconnected-(XESS-L3-Pad46)") (class "Default")
      (node (ref "XESS") (pin "46") (pinfunction "L3_46") (pintype "bidirectional"))
    )
    (net (code "335") (name "unconnected-(XESS-L15-Pad79)") (class "Default")
      (node (ref "XESS") (pin "79") (pinfunction "L15_79") (pintype "bidirectional"))
    )
    (net (code "336") (name "unconnected-(XESS-M1-Pad47)") (class "Default")
      (node (ref "XESS") (pin "47") (pinfunction "M1_47") (pintype "bidirectional"))
    )
    (net (code "337") (name "unconnected-(XESS-M2-Pad48)") (class "Default")
      (node (ref "XESS") (pin "48") (pinfunction "M2_48") (pintype "bidirectional"))
    )
    (net (code "338") (name "unconnected-(XESS-M15-Pad78)") (class "Default")
      (node (ref "XESS") (pin "78") (pinfunction "M15_78") (pintype "bidirectional"))
    )
    (net (code "339") (name "unconnected-(XESS-N15-Pad77)") (class "Default")
      (node (ref "XESS") (pin "77") (pinfunction "N15_77") (pintype "bidirectional"))
    )
    (net (code "340") (name "unconnected-(XESS-P$53-Pad53)") (class "Default")
      (node (ref "XESS") (pin "53") (pinfunction "P$53_53") (pintype "bidirectional"))
    )
    (net (code "341") (name "unconnected-(XESS-P$63-Pad63)") (class "Default")
      (node (ref "XESS") (pin "63") (pinfunction "P$63_63") (pintype "bidirectional"))
    )
    (net (code "342") (name "unconnected-(XESS-P$65-Pad65)") (class "Default")
      (node (ref "XESS") (pin "65") (pinfunction "P$65_65") (pintype "bidirectional"))
    )
    (net (code "343") (name "unconnected-(XESS-P$72-Pad72)") (class "Default")
      (node (ref "XESS") (pin "72") (pinfunction "P$72_72") (pintype "bidirectional"))
    )
    (net (code "344") (name "unconnected-(XESS-P$73-Pad73)") (class "Default")
      (node (ref "XESS") (pin "73") (pinfunction "P$73_73") (pintype "bidirectional"))
    )
    (net (code "345") (name "unconnected-(XESS-P$74-Pad74)") (class "Default")
      (node (ref "XESS") (pin "74") (pinfunction "P$74_74") (pintype "bidirectional"))
    )
    (net (code "346") (name "unconnected-(XESS-P$75-Pad75)") (class "Default")
      (node (ref "XESS") (pin "75") (pinfunction "P$75_75") (pintype "bidirectional"))
    )
    (net (code "347") (name "unconnected-(XESS-P$76-Pad76)") (class "Default")
      (node (ref "XESS") (pin "76") (pinfunction "P$76_76") (pintype "bidirectional"))
    )
    (net (code "348") (name "unconnected-(XESS-PROG#-Pad55)") (class "Default")
      (node (ref "XESS") (pin "55") (pinfunction "PROG#_55") (pintype "bidirectional"))
    )
    (net (code "349") (name "unconnected-(XESS-TCK-Pad16)") (class "Default")
      (node (ref "XESS") (pin "16") (pinfunction "TCK_16") (pintype "bidirectional"))
    )
    (net (code "350") (name "unconnected-(XESS-WR#-Pad30)") (class "Default")
      (node (ref "XESS") (pin "30") (pinfunction "WR#_30") (pintype "bidirectional"))
    )
    (net (code "351") (name "~{3S-SCL}") (class "Default")
      (node (ref "IC17") (pin "11") (pinfunction "A1_11") (pintype "input"))
      (node (ref "IC17") (pin "8") (pinfunction "A4_8") (pintype "input"))
      (node (ref "XESS") (pin "60") (pinfunction "N3_60") (pintype "bidirectional"))
    )
    (net (code "352") (name "~{SCL}") (class "Default")
      (node (ref "IC1") (pin "10") (pinfunction "SCL_10") (pintype "input"))
      (node (ref "IC10") (pin "10") (pinfunction "SCL_10") (pintype "input"))
      (node (ref "IC11") (pin "10") (pinfunction "SCL_10") (pintype "input"))
      (node (ref "IC12") (pin "10") (pinfunction "SCL_10") (pintype "input"))
      (node (ref "IC13") (pin "10") (pinfunction "SCL_10") (pintype "input"))
      (node (ref "IC14") (pin "1") (pinfunction "SH/~{LD}_1") (pintype "input"))
      (node (ref "IC15") (pin "1") (pinfunction "SH/~{LD}_1") (pintype "input"))
      (node (ref "IC16") (pin "10") (pinfunction "SCL_10") (pintype "input"))
      (node (ref "IC17") (pin "12") (pinfunction "Y4_12") (pintype "tri_state"))
      (node (ref "IC17") (pin "9") (pinfunction "Y1_9") (pintype "tri_state"))
      (node (ref "IC18") (pin "1") (pinfunction "SH/~{LD}_1") (pintype "input"))
      (node (ref "IC2") (pin "1") (pinfunction "SH/~{LD}_1") (pintype "input"))
      (node (ref "IC4") (pin "10") (pinfunction "SCL_10") (pintype "input"))
      (node (ref "IC5") (pin "10") (pinfunction "SCL_10") (pintype "input"))
      (node (ref "IC6") (pin "10") (pinfunction "SCL_10") (pintype "input"))
      (node (ref "IC7") (pin "10") (pinfunction "SCL_10") (pintype "input"))
      (node (ref "IC8") (pin "10") (pinfunction "SCL_10") (pintype "input"))
      (node (ref "IC9") (pin "10") (pinfunction "SCL_10") (pintype "input"))
      (node (ref "SV1") (pin "5") (pinfunction "5_5") (pintype "passive"))
      (node (ref "SV2") (pin "5") (pinfunction "5_5") (pintype "passive"))
    )
  )
)
